# PLC-_-_-V1.net
KiCad netlist of a schematic drawn in Altium Designer
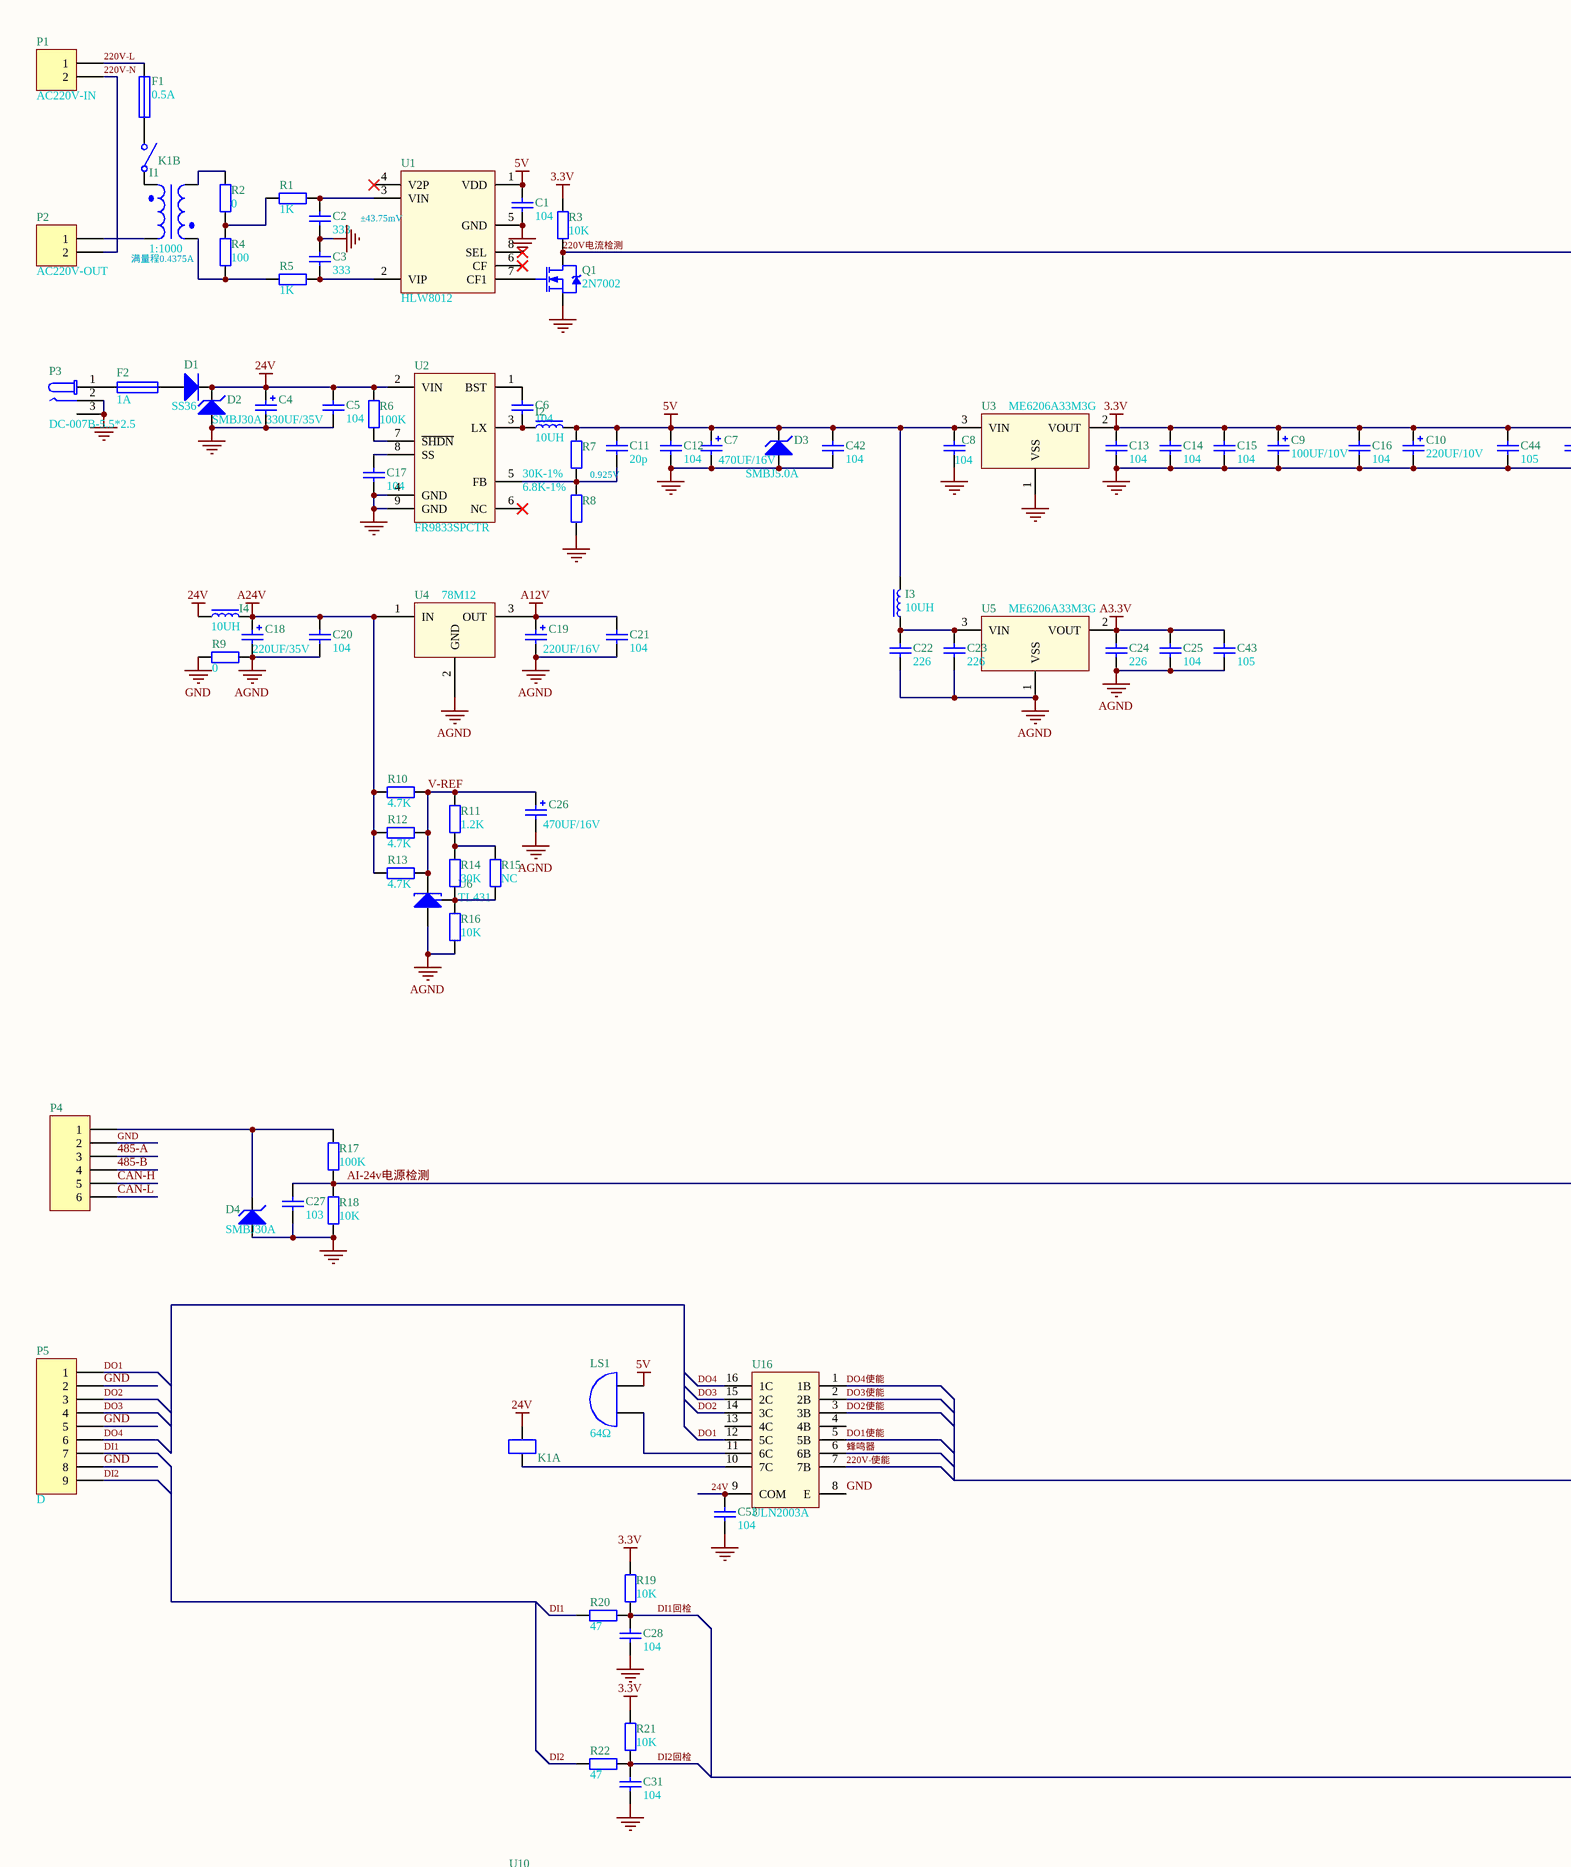
[diagram p0: PLC-无线通讯版-检测板-V1.SchDoc, top left]
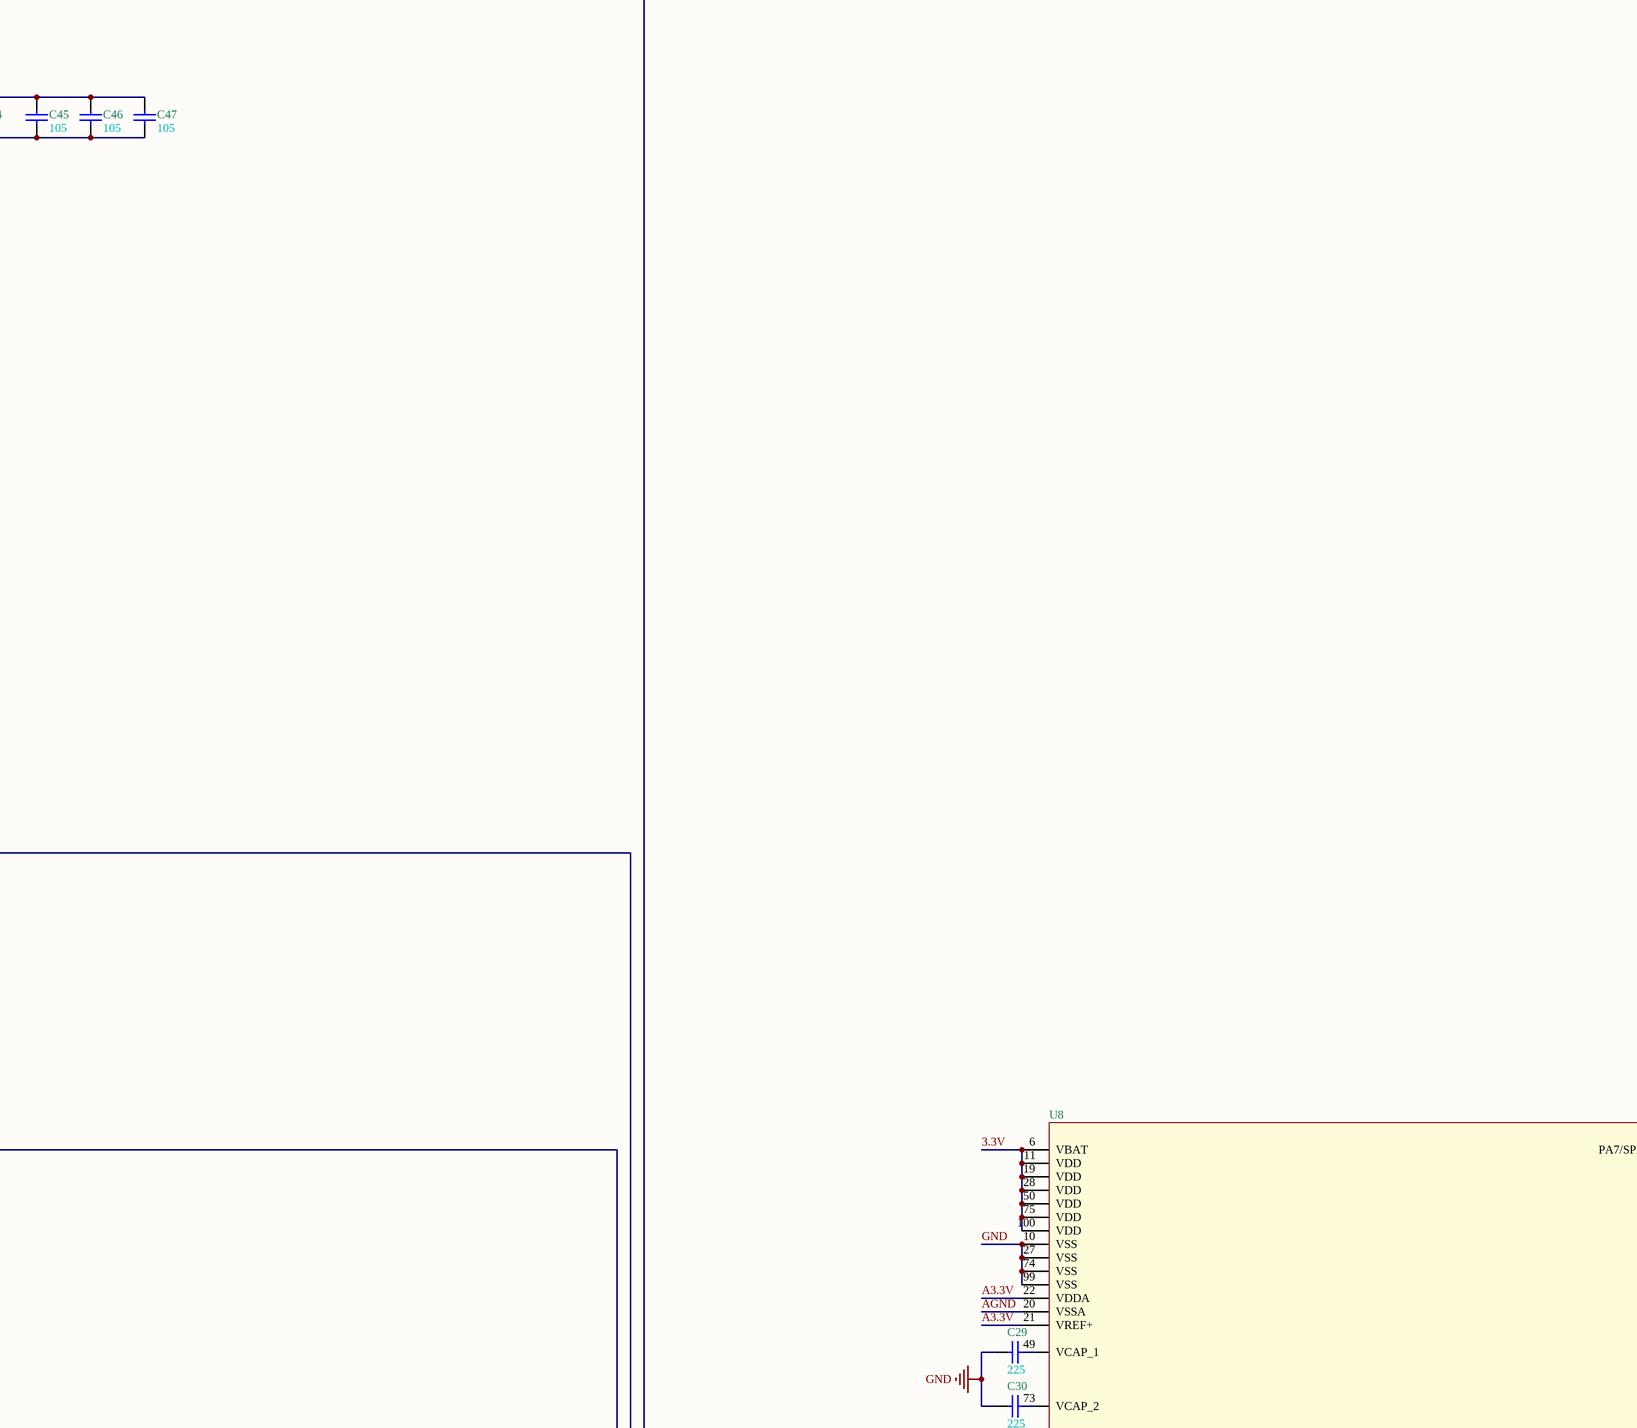
[diagram p1: PLC-无线通讯版-检测板-V1.SchDoc, top middle]
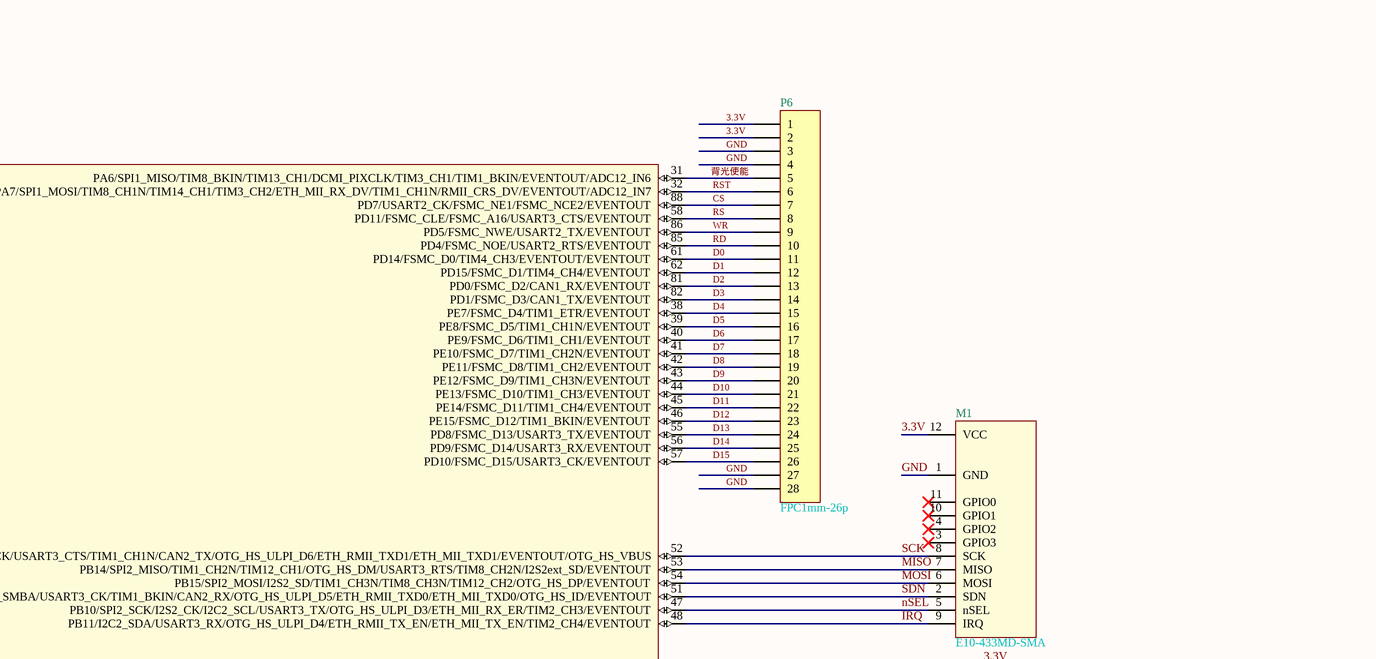
[diagram p2: PLC-无线通讯版-检测板-V1.SchDoc, top right]
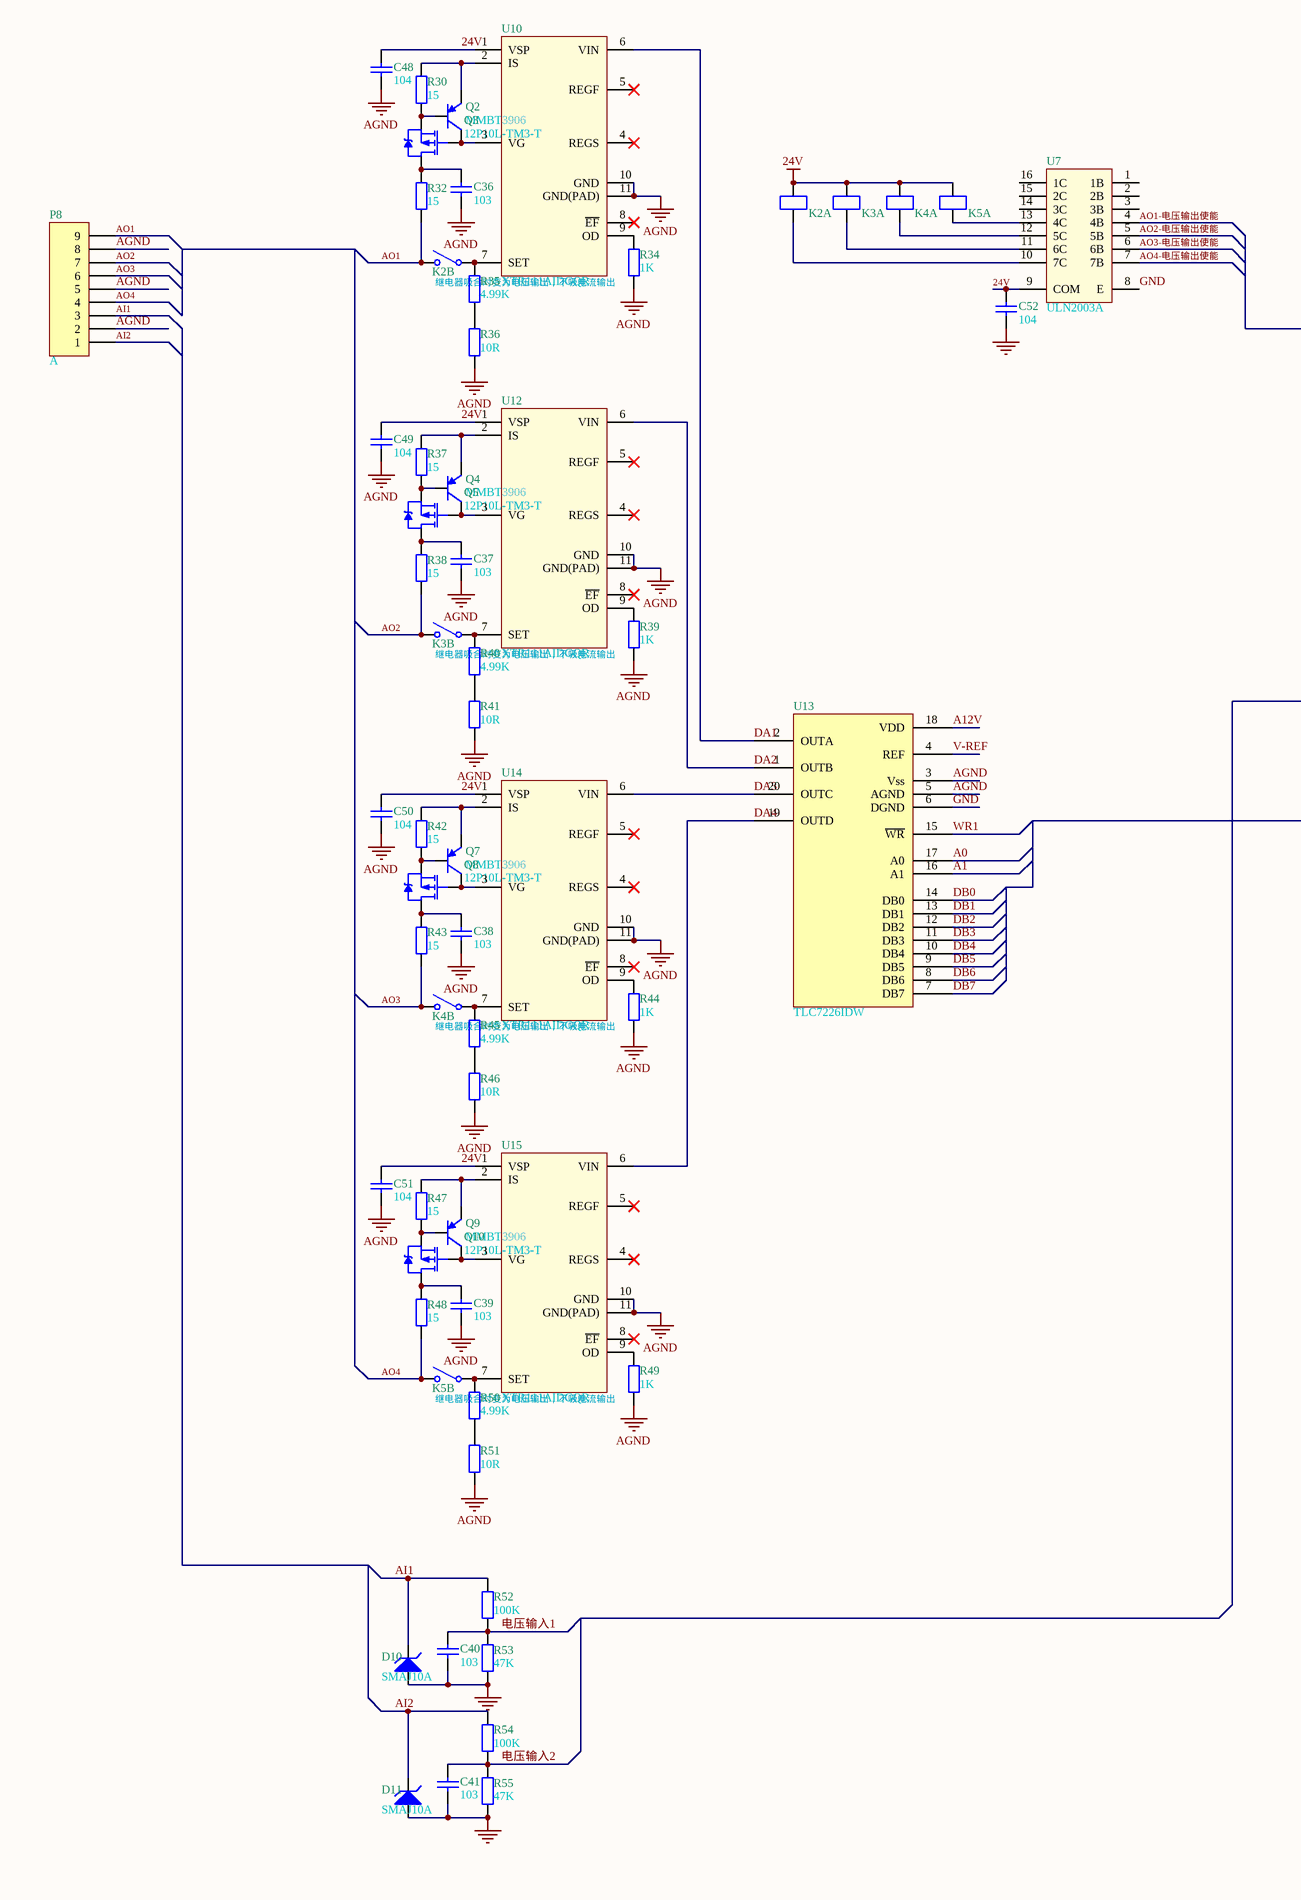
[diagram p3: PLC-无线通讯版-检测板-V1.SchDoc, bottom left]
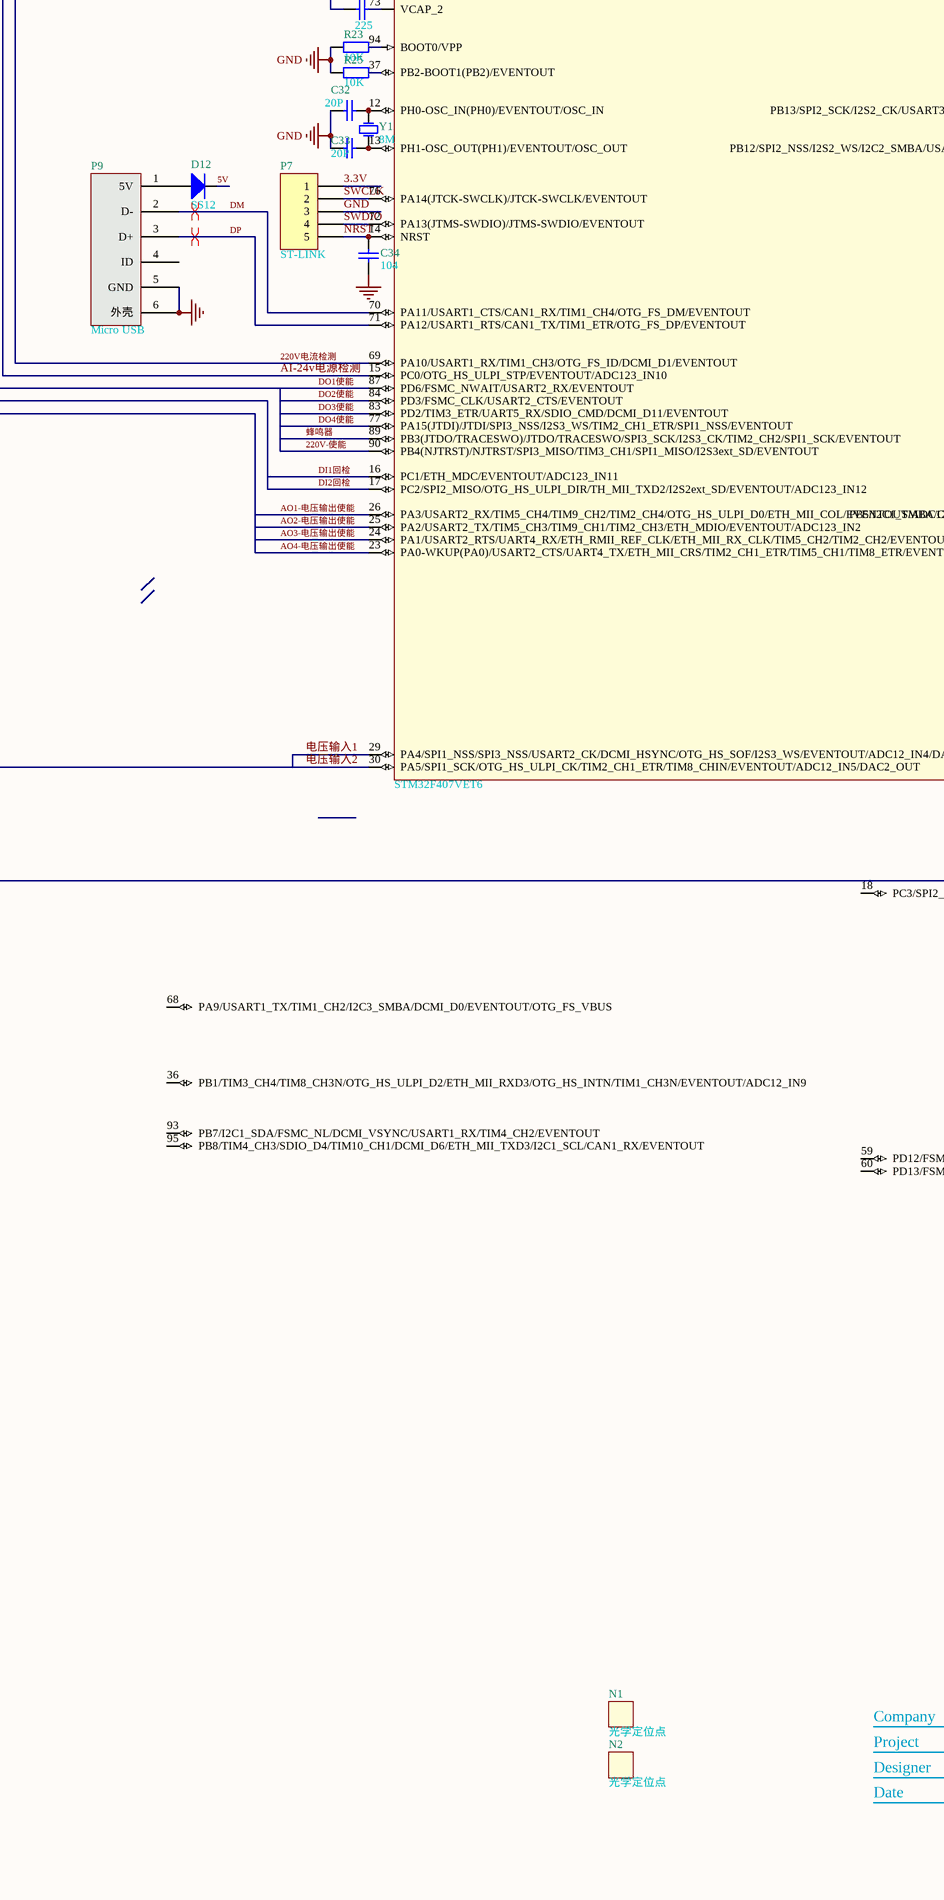
[diagram p4: PLC-无线通讯版-检测板-V1.SchDoc, bottom middle]
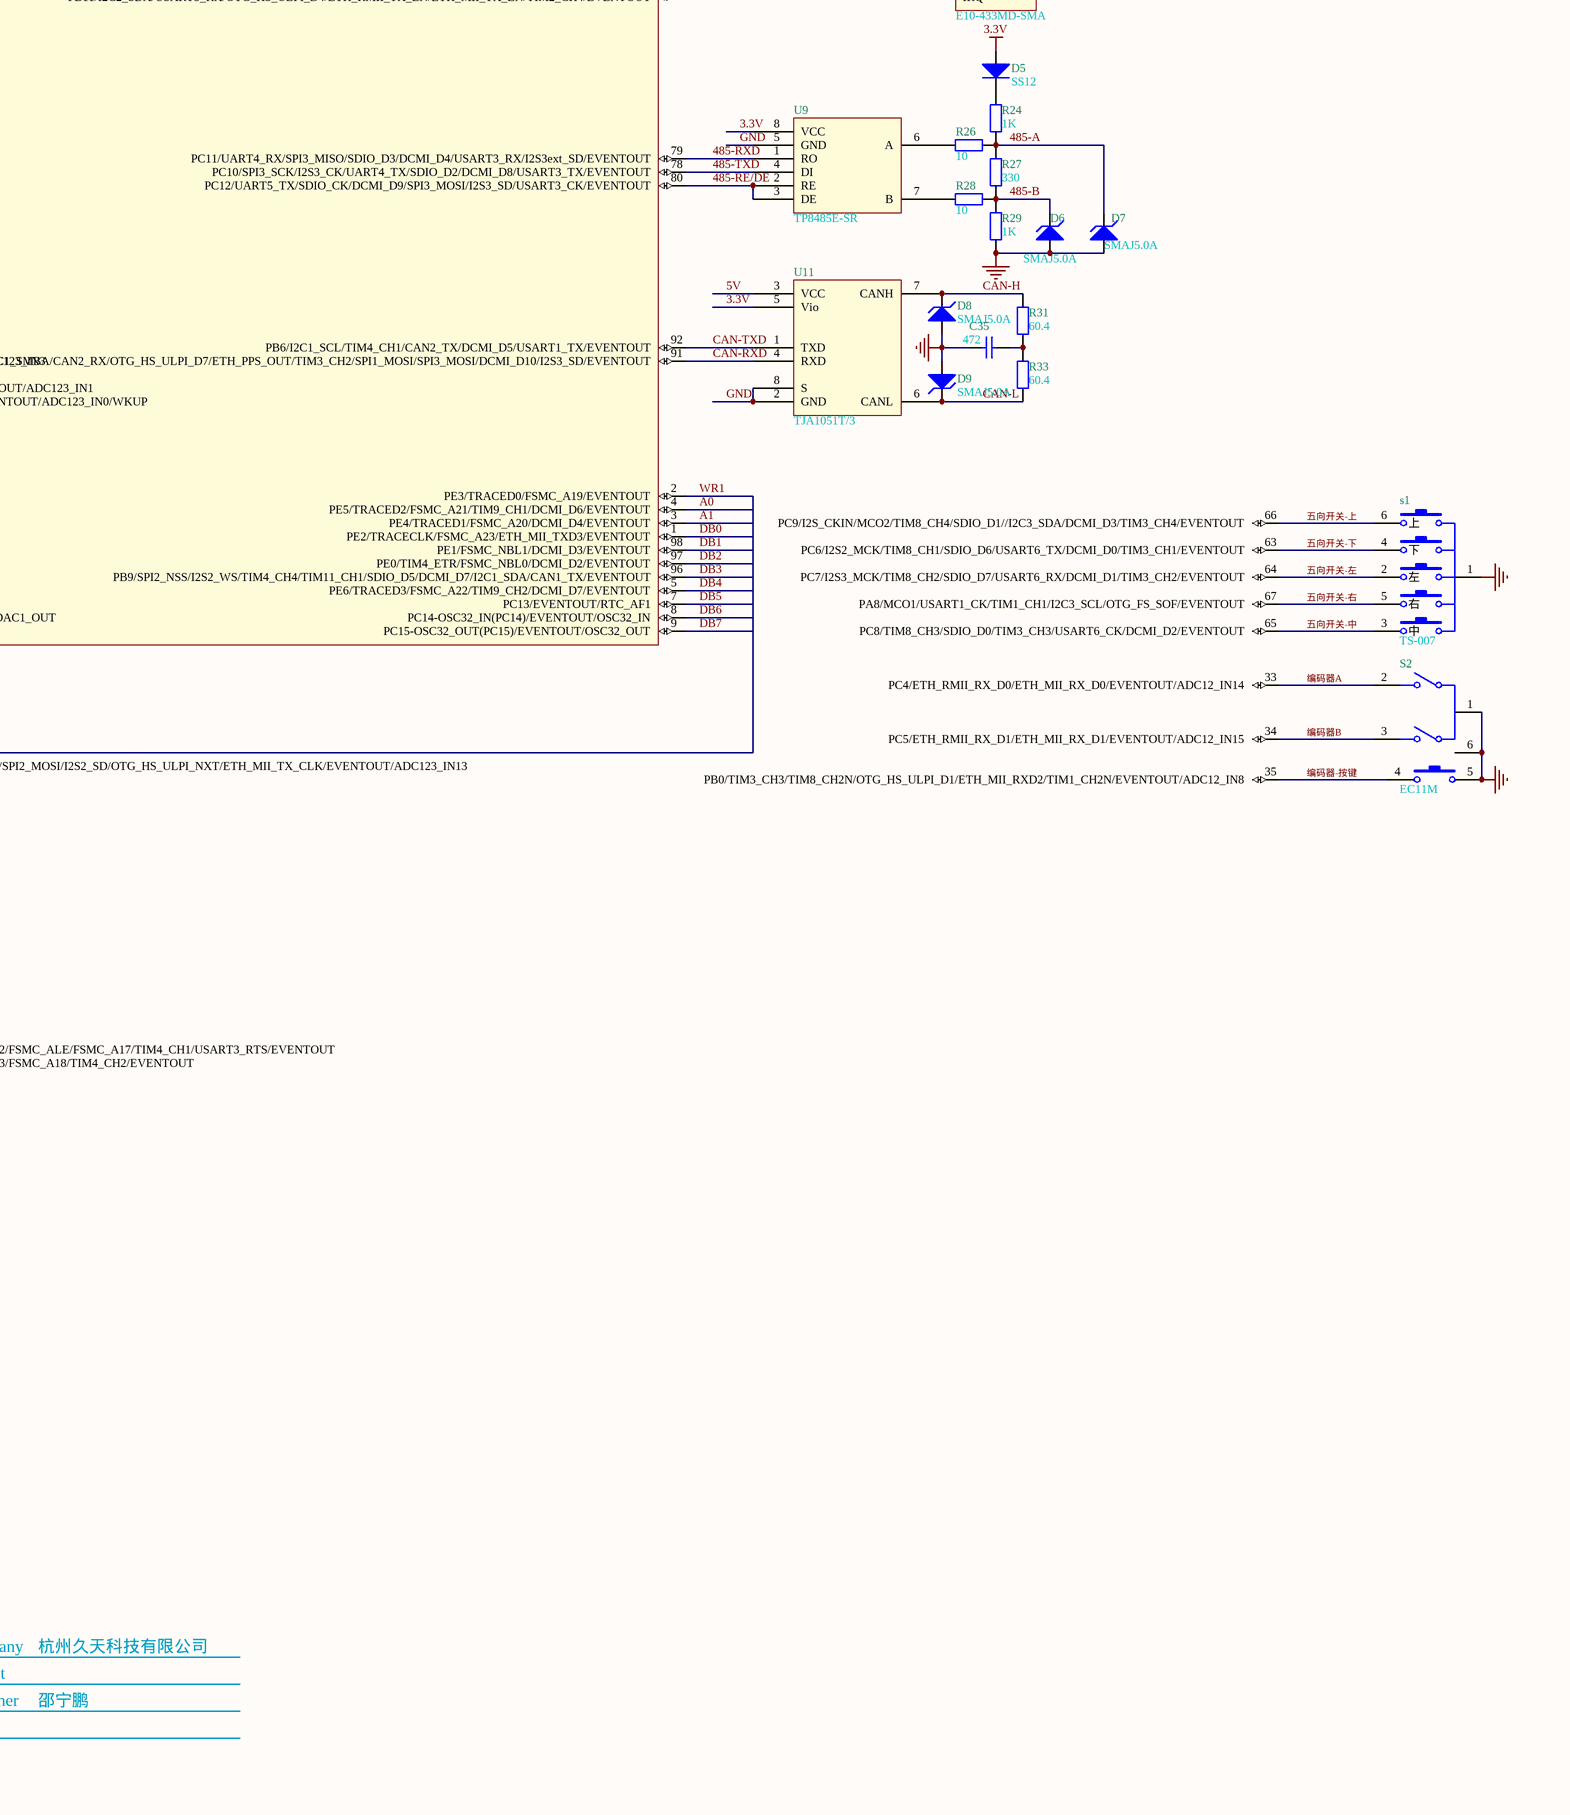
[diagram p5: PLC-无线通讯版-检测板-V1.SchDoc, bottom right]

(export (version "E")
  (design (tool "Eeschema 10.0.6"))
  (components
    (comp (ref "C1")
      (value "104")
      (footprint "C-0603")
      (description "Capacitor")
      (fields (field (name "PUBLISHER") "Altium Limited"))
      (libsource (lib "元件2.0") (part "Cap"))
    )
    (comp (ref "C2")
      (value "333")
      (footprint "C-0603")
      (description "Capacitor")
      (fields (field (name "PUBLISHER") "Altium Limited"))
      (libsource (lib "元件2.0") (part "Cap"))
    )
    (comp (ref "C3")
      (value "333")
      (footprint "C-0603")
      (description "Capacitor")
      (fields (field (name "PUBLISHER") "Altium Limited"))
      (libsource (lib "元件2.0") (part "Cap"))
    )
    (comp (ref "C4")
      (value "330UF/35V")
      (footprint "贴片固态电容8*10-M")
      (description "电解电容")
      (fields (field (name "PUBLISHER") "Altium Limited"))
      (libsource (lib "2电容-V1.0") (part "Cap Pol1"))
    )
    (comp (ref "C5")
      (value "104")
      (footprint "C-0603")
      (description "Capacitor")
      (fields (field (name "PUBLISHER") "Altium Limited"))
      (libsource (lib "元件2.0") (part "Cap"))
    )
    (comp (ref "C6")
      (value "104")
      (footprint "C-0603")
      (description "Capacitor")
      (fields (field (name "PUBLISHER") "Altium Limited"))
      (libsource (lib "元件2.0") (part "Cap"))
    )
    (comp (ref "C7")
      (value "470UF/16V")
      (footprint "贴片固态电容8*10-M")
      (description "Polarized Capacitor (Radial)")
      (fields (field (name "PUBLISHER") "Altium Limited"))
      (libsource (lib "元件2.0") (part "Cap Pol1"))
    )
    (comp (ref "C8")
      (value "104")
      (footprint "C-0603")
      (description "Capacitor")
      (fields (field (name "PUBLISHER") "Altium Limited"))
      (libsource (lib "元件2.0") (part "Cap"))
    )
    (comp (ref "C9")
      (value "100UF/10V")
      (footprint "贴片固态电容5*5.3")
      (description "Polarized Capacitor (Radial)")
      (fields (field (name "PUBLISHER") "Altium Limited"))
      (libsource (lib "元件2.0") (part "Cap Pol1"))
    )
    (comp (ref "C10")
      (value "220UF/10V")
      (footprint "贴片固态电容6.3*5.3-M")
      (description "Polarized Capacitor (Radial)")
      (fields (field (name "PUBLISHER") "Altium Limited"))
      (libsource (lib "元件2.0") (part "Cap Pol1"))
    )
    (comp (ref "C11")
      (value "20p")
      (footprint "C-0603")
      (description "Capacitor")
      (fields (field (name "PUBLISHER") "Altium Limited"))
      (libsource (lib "元件2.0") (part "Cap"))
    )
    (comp (ref "C12")
      (value "104")
      (footprint "C-0603")
      (description "Capacitor")
      (fields (field (name "PUBLISHER") "Altium Limited"))
      (libsource (lib "元件2.0") (part "Cap"))
    )
    (comp (ref "C13")
      (value "104")
      (footprint "C-0603")
      (description "Capacitor")
      (fields (field (name "PUBLISHER") "Altium Limited"))
      (libsource (lib "元件2.0") (part "Cap"))
    )
    (comp (ref "C14")
      (value "104")
      (footprint "C-0603")
      (description "Capacitor")
      (fields (field (name "PUBLISHER") "Altium Limited"))
      (libsource (lib "元件2.0") (part "Cap"))
    )
    (comp (ref "C15")
      (value "104")
      (footprint "C-0603")
      (description "Capacitor")
      (fields (field (name "PUBLISHER") "Altium Limited"))
      (libsource (lib "元件2.0") (part "Cap"))
    )
    (comp (ref "C16")
      (value "104")
      (footprint "C-0603")
      (description "Capacitor")
      (fields (field (name "PUBLISHER") "Altium Limited"))
      (libsource (lib "元件2.0") (part "Cap"))
    )
    (comp (ref "C17")
      (value "104")
      (footprint "C-0603")
      (description "Capacitor")
      (fields (field (name "PUBLISHER") "Altium Limited"))
      (libsource (lib "元件2.0") (part "Cap"))
    )
    (comp (ref "C18")
      (value "220UF/35V")
      (footprint "贴片固态电容8*10-M")
      (description "电解电容")
      (fields (field (name "PUBLISHER") "Altium Limited"))
      (libsource (lib "2电容-V1.0") (part "Cap Pol1"))
    )
    (comp (ref "C19")
      (value "220UF/16V")
      (footprint "贴片固态电容6.3*7.7")
      (description "Polarized Capacitor (Radial)")
      (fields (field (name "PUBLISHER") "Altium Limited"))
      (libsource (lib "元件2.0") (part "Cap Pol1"))
    )
    (comp (ref "C20")
      (value "104")
      (footprint "C-0603")
      (description "Capacitor")
      (fields (field (name "PUBLISHER") "Altium Limited"))
      (libsource (lib "元件2.0") (part "Cap"))
    )
    (comp (ref "C21")
      (value "104")
      (footprint "C-0603")
      (description "Capacitor")
      (fields (field (name "PUBLISHER") "Altium Limited"))
      (libsource (lib "元件2.0") (part "Cap"))
    )
    (comp (ref "C22")
      (value "226")
      (footprint "C-0805")
      (description "Capacitor")
      (fields (field (name "PUBLISHER") "Altium Limited"))
      (libsource (lib "元件2.0") (part "Cap"))
    )
    (comp (ref "C23")
      (value "226")
      (footprint "C-0805")
      (description "Capacitor")
      (fields (field (name "PUBLISHER") "Altium Limited"))
      (libsource (lib "元件2.0") (part "Cap"))
    )
    (comp (ref "C24")
      (value "226")
      (footprint "C-0805")
      (description "Capacitor")
      (fields (field (name "PUBLISHER") "Altium Limited"))
      (libsource (lib "元件2.0") (part "Cap"))
    )
    (comp (ref "C25")
      (value "104")
      (footprint "C-0603")
      (description "Capacitor")
      (fields (field (name "PUBLISHER") "Altium Limited"))
      (libsource (lib "元件2.0") (part "Cap"))
    )
    (comp (ref "C26")
      (value "470UF/16V")
      (footprint "贴片固态电容8*10-M")
      (description "Polarized Capacitor (Radial)")
      (fields (field (name "PUBLISHER") "Altium Limited"))
      (libsource (lib "元件2.0") (part "Cap Pol1"))
    )
    (comp (ref "C27")
      (value "103")
      (footprint "C-0603")
      (description "0805")
      (fields (field (name "PUBLISHER") "Altium Limited"))
      (libsource (lib "2电容-V1.0") (part "Cap-0603"))
    )
    (comp (ref "C28")
      (value "104")
      (footprint "C-0603")
      (description "0805")
      (fields (field (name "PUBLISHER") "Altium Limited"))
      (libsource (lib "2电容-V1.0") (part "Cap-0603"))
    )
    (comp (ref "C29")
      (value "225")
      (footprint "C-0603")
      (description "0805")
      (fields (field (name "PUBLISHER") "Altium Limited"))
      (libsource (lib "2电容-V1.0") (part "Cap-0603"))
    )
    (comp (ref "C30")
      (value "225")
      (footprint "C-0603")
      (description "0805")
      (fields (field (name "PUBLISHER") "Altium Limited"))
      (libsource (lib "2电容-V1.0") (part "Cap-0603"))
    )
    (comp (ref "C31")
      (value "104")
      (footprint "C-0603")
      (description "0805")
      (fields (field (name "PUBLISHER") "Altium Limited"))
      (libsource (lib "2电容-V1.0") (part "Cap-0603"))
    )
    (comp (ref "C32")
      (value "20P")
      (footprint "C-0603")
      (description "0805")
      (fields (field (name "PUBLISHER") "Altium Limited"))
      (libsource (lib "2电容-V1.0") (part "Cap-0603"))
    )
    (comp (ref "C33")
      (value "20P")
      (footprint "C-0603")
      (description "0805")
      (fields (field (name "PUBLISHER") "Altium Limited"))
      (libsource (lib "2电容-V1.0") (part "Cap-0603"))
    )
    (comp (ref "C34")
      (value "104")
      (footprint "C-0603")
      (description "0805")
      (fields (field (name "PUBLISHER") "Altium Limited"))
      (libsource (lib "2电容-V1.0") (part "Cap-0603"))
    )
    (comp (ref "C35")
      (value "472")
      (footprint "C-0603")
      (description "0805")
      (fields (field (name "PUBLISHER") "Altium Limited"))
      (libsource (lib "2电容-V1.0") (part "Cap-0603"))
    )
    (comp (ref "C36")
      (value "103")
      (footprint "C-0603")
      (description "0805")
      (fields (field (name "PUBLISHER") "Altium Limited"))
      (libsource (lib "2电容-V1.0") (part "Cap-0603"))
    )
    (comp (ref "C37")
      (value "103")
      (footprint "C-0603")
      (description "0805")
      (fields (field (name "PUBLISHER") "Altium Limited"))
      (libsource (lib "2电容-V1.0") (part "Cap-0603"))
    )
    (comp (ref "C38")
      (value "103")
      (footprint "C-0603")
      (description "0805")
      (fields (field (name "PUBLISHER") "Altium Limited"))
      (libsource (lib "2电容-V1.0") (part "Cap-0603"))
    )
    (comp (ref "C39")
      (value "103")
      (footprint "C-0603")
      (description "0805")
      (fields (field (name "PUBLISHER") "Altium Limited"))
      (libsource (lib "2电容-V1.0") (part "Cap-0603"))
    )
    (comp (ref "C40")
      (value "103")
      (footprint "C-0603")
      (description "0805")
      (fields (field (name "PUBLISHER") "Altium Limited"))
      (libsource (lib "2电容-V1.0") (part "Cap-0603"))
    )
    (comp (ref "C41")
      (value "103")
      (footprint "C-0603")
      (description "0805")
      (fields (field (name "PUBLISHER") "Altium Limited"))
      (libsource (lib "2电容-V1.0") (part "Cap-0603"))
    )
    (comp (ref "C42")
      (value "104")
      (footprint "C-0603")
      (description "Capacitor")
      (fields (field (name "PUBLISHER") "Altium Limited"))
      (libsource (lib "元件2.0") (part "Cap"))
    )
    (comp (ref "C43")
      (value "105")
      (footprint "C-0603")
      (description "Capacitor")
      (fields (field (name "PUBLISHER") "Altium Limited"))
      (libsource (lib "元件2.0") (part "Cap"))
    )
    (comp (ref "C44")
      (value "105")
      (footprint "C-0603")
      (description "Capacitor")
      (fields (field (name "PUBLISHER") "Altium Limited"))
      (libsource (lib "元件2.0") (part "Cap"))
    )
    (comp (ref "C45")
      (value "105")
      (footprint "C-0603")
      (description "Capacitor")
      (fields (field (name "PUBLISHER") "Altium Limited"))
      (libsource (lib "元件2.0") (part "Cap"))
    )
    (comp (ref "C46")
      (value "105")
      (footprint "C-0603")
      (description "Capacitor")
      (fields (field (name "PUBLISHER") "Altium Limited"))
      (libsource (lib "元件2.0") (part "Cap"))
    )
    (comp (ref "C47")
      (value "105")
      (footprint "C-0603")
      (description "Capacitor")
      (fields (field (name "PUBLISHER") "Altium Limited"))
      (libsource (lib "元件2.0") (part "Cap"))
    )
    (comp (ref "C48")
      (value "104")
      (footprint "C-0603")
      (description "Capacitor")
      (fields (field (name "PUBLISHER") "Altium Limited"))
      (libsource (lib "元件2.0") (part "Cap"))
    )
    (comp (ref "C49")
      (value "104")
      (footprint "C-0603")
      (description "Capacitor")
      (fields (field (name "PUBLISHER") "Altium Limited"))
      (libsource (lib "元件2.0") (part "Cap"))
    )
    (comp (ref "C50")
      (value "104")
      (footprint "C-0603")
      (description "Capacitor")
      (fields (field (name "PUBLISHER") "Altium Limited"))
      (libsource (lib "元件2.0") (part "Cap"))
    )
    (comp (ref "C51")
      (value "104")
      (footprint "C-0603")
      (description "Capacitor")
      (fields (field (name "PUBLISHER") "Altium Limited"))
      (libsource (lib "元件2.0") (part "Cap"))
    )
    (comp (ref "C52")
      (value "104")
      (footprint "C-0603")
      (description "Capacitor")
      (fields (field (name "PUBLISHER") "Altium Limited"))
      (libsource (lib "元件2.0") (part "Cap"))
    )
    (comp (ref "C53")
      (value "104")
      (footprint "C-0603")
      (description "Capacitor")
      (fields (field (name "PUBLISHER") "Altium Limited"))
      (libsource (lib "元件2.0") (part "Cap"))
    )
    (comp (ref "D1")
      (value "SS36")
      (footprint "SMB")
      (description "SMB")
      (fields (field (name "PUBLISHER") "Altium Limited"))
      (libsource (lib "4二极管-V1.1") (part "SS36"))
    )
    (comp (ref "D2")
      (value "SMBJ30A")
      (footprint "SMB-N")
      (description "SMB")
      (libsource (lib "4二极管-V1.1") (part "TVS-1"))
    )
    (comp (ref "D3")
      (value "SMBJ5.0A")
      (footprint "SMB-N")
      (description "SMB")
      (libsource (lib "4二极管-V1.1") (part "TVS-1"))
    )
    (comp (ref "D4")
      (value "SMBJ30A")
      (footprint "SMB")
      (description "SMB")
      (libsource (lib "4二极管-V1.1") (part "TVS-1"))
    )
    (comp (ref "D5")
      (value "SS12")
      (footprint "SOD-523/0603")
      (description "SMA")
      (libsource (lib "4二极管-V1.1") (part "SS14"))
    )
    (comp (ref "D6")
      (value "SMAJ5.0A")
      (footprint "SMA")
      (description "SMB")
      (libsource (lib "4二极管-V1.1") (part "TVS-1"))
    )
    (comp (ref "D7")
      (value "SMAJ5.0A")
      (footprint "SMA")
      (description "SMB")
      (libsource (lib "4二极管-V1.1") (part "TVS-1"))
    )
    (comp (ref "D8")
      (value "SMAJ5.0A")
      (footprint "SMA")
      (description "SMB")
      (libsource (lib "4二极管-V1.1") (part "TVS-1"))
    )
    (comp (ref "D9")
      (value "SMAJ5.0A")
      (footprint "SMA")
      (description "SMB")
      (libsource (lib "4二极管-V1.1") (part "TVS-1"))
    )
    (comp (ref "D10")
      (value "SMAJ10A")
      (footprint "SMA")
      (description "SMB")
      (libsource (lib "4二极管-V1.1") (part "TVS-1"))
    )
    (comp (ref "D11")
      (value "SMAJ10A")
      (footprint "SMA")
      (description "SMB")
      (libsource (lib "4二极管-V1.1") (part "TVS-1"))
    )
    (comp (ref "D12")
      (value "SS12")
      (footprint "SMA")
      (description "SMA")
      (libsource (lib "4二极管-V1.1") (part "SS14"))
    )
    (comp (ref "F1")
      (value "0.5A")
      (footprint "FUSE-3*10带引线")
      (description "Fuse")
      (fields (field (name "PUBLISHER") "Altium Limited"))
      (libsource (lib "11其他元件-V1.0") (part "Fuse 1"))
    )
    (comp (ref "F2")
      (value "1A")
      (footprint "FUSE-1808保险丝座")
      (description "Fuse")
      (fields (field (name "PUBLISHER") "Altium Limited"))
      (libsource (lib "11其他元件-V1.0") (part "Fuse 1"))
    )
    (comp (ref "I1") (value "1:1000") (footprint "EI19*6.5电流互感器") (libsource (lib "3电感-V1.0") (part "电流互感器")))
    (comp (ref "I2")
      (value "10UH")
      (footprint "一体成型电感0630")
      (libsource (lib "3电感-V1.0") (part "Inductance3"))
    )
    (comp (ref "I3") (value "10UH") (footprint "SWPA4030S") (libsource (lib "3电感-V1.0") (part "Inductance3")))
    (comp (ref "I4") (value "10UH") (footprint "SWPA4030S") (libsource (lib "3电感-V1.0") (part "Inductance3")))
    (comp (ref "K1")
      (value "HF49FD-D24-1H11")
      (footprint "HF49FD-D24-1H11")
      (libsource (lib "") (part "HF49FD-D24-1H11_1"))
    )
    (comp (ref "K2")
      (value "HF49FD-D24-1H11")
      (footprint "HF49FD-D24-1H11")
      (libsource (lib "10继电器-V1.0") (part "HF49FD-D24-1H11"))
    )
    (comp (ref "K3")
      (value "HF49FD-D24-1H11")
      (footprint "HF49FD-D24-1H11")
      (libsource (lib "10继电器-V1.0") (part "HF49FD-D24-1H11"))
    )
    (comp (ref "K4")
      (value "HF49FD-D24-1H11")
      (footprint "HF49FD-D24-1H11")
      (libsource (lib "") (part "HF49FD-D24-1H11_1"))
    )
    (comp (ref "K5")
      (value "HF49FD-D24-1H11")
      (footprint "HF49FD-D24-1H11")
      (libsource (lib "") (part "HF49FD-D24-1H11_1"))
    )
    (comp (ref "LS1")
      (value "64Ω")
      (footprint "蜂鸣器 无源 12*8.2")
      (description "Electrical Bell")
      (fields (field (name "PUBLISHER") "Altium Limited"))
      (libsource (lib "11其他元件-V1.0") (part "Bell"))
    )
    (comp (ref "M1")
      (value "E10-433MD-SMA")
      (footprint "E10-433MD-SMA")
      (libsource (lib "6电路模块-V1.0") (part "E10-433MD-SMA"))
    )
    (comp (ref "N1") (value "光学定位点") (footprint "MARK-1mm-3mm") (libsource (lib "11其他元件-V1.0") (part "无引脚")))
    (comp (ref "N2") (value "光学定位点") (footprint "MARK-1mm-3mm") (libsource (lib "11其他元件-V1.0") (part "无引脚")))
    (comp (ref "P1")
      (value "AC220V-IN")
      (footprint "KF2EDGVC-5.08-2P")
      (description "Header, 2-Pin")
      (fields (field (name "PUBLISHER") "Altium Limited"))
      (libsource (lib "5排针-V1.0") (part "Header 2"))
    )
    (comp (ref "P2")
      (value "AC220V-OUT")
      (footprint "KF2EDGVC-5.08-2P")
      (description "Header, 2-Pin")
      (fields (field (name "PUBLISHER") "Altium Limited"))
      (libsource (lib "5排针-V1.0") (part "Header 2"))
    )
    (comp (ref "P3")
      (value "DC-007B-5.5*2.5")
      (footprint "DC-007B")
      (libsource (lib "PJ系列") (part "DC-007B"))
    )
    (comp (ref "P4")
      (value "~")
      (footprint "2EMGKG-5.08-6P")
      (description "Header, 6-Pin")
      (fields (field (name "PUBLISHER") "Altium Limited"))
      (libsource (lib "5排针-V1.0") (part "Header 6"))
    )
    (comp (ref "P5")
      (value "D")
      (footprint "2EMGKG-5.08-9P")
      (description "Header, 9-Pin")
      (fields (field (name "PUBLISHER") "Altium Limited"))
      (libsource (lib "") (part "Header 9_1"))
    )
    (comp (ref "P6")
      (value "FPC1mm-26p")
      (footprint "FPC-0.5mm_26P下接翻盖")
      (description "Header, 28-Pin")
      (fields (field (name "PUBLISHER") "Altium Limited"))
      (libsource (lib "5排针-V1.0") (part "Header 28"))
    )
    (comp (ref "P7")
      (value "ST-LINK")
      (footprint "HDR1X5")
      (description "Header, 5-Pin")
      (fields (field (name "PUBLISHER") "Altium Limited"))
      (libsource (lib "5排针-V1.0") (part "Header 5"))
    )
    (comp (ref "P8")
      (value "A")
      (footprint "2EMGKG-5.08-9P")
      (description "Header, 9-Pin")
      (fields (field (name "PUBLISHER") "Altium Limited"))
      (libsource (lib "5排针-V1.0") (part "Header 9"))
    )
    (comp (ref "P9")
      (value "Micro USB")
      (footprint "MICRO-USB-牛角插板-无卷边")
      (libsource (lib "11其他元件-V1.0") (part "USB-5_A"))
    )
    (comp (ref "Q1") (value "2N7002") (footprint "SOT-23") (libsource (lib "4二极管-V1.1") (part "2N7002")))
    (comp (ref "Q2")
      (value "MMBT3906")
      (footprint "SOT-23")
      (description "PNP SOT-23")
      (fields (field (name "PUBLISHER") "Altium Limited"))
      (libsource (lib "4二极管-V1.1") (part "S8550"))
    )
    (comp (ref "Q3")
      (value "12P10L-TM3-T")
      (footprint "TO-251-N")
      (libsource (lib "4二极管-V1.1") (part "12P10L-TM3-T"))
    )
    (comp (ref "Q4")
      (value "MMBT3906")
      (footprint "SOT-23")
      (description "PNP SOT-23")
      (fields (field (name "PUBLISHER") "Altium Limited"))
      (libsource (lib "4二极管-V1.1") (part "S8550"))
    )
    (comp (ref "Q5")
      (value "12P10L-TM3-T")
      (footprint "TO-251-N")
      (libsource (lib "4二极管-V1.1") (part "12P10L-TM3-T"))
    )
    (comp (ref "Q7")
      (value "MMBT3906")
      (footprint "SOT-23")
      (description "PNP SOT-23")
      (fields (field (name "PUBLISHER") "Altium Limited"))
      (libsource (lib "4二极管-V1.1") (part "S8550"))
    )
    (comp (ref "Q8")
      (value "12P10L-TM3-T")
      (footprint "TO-251-N")
      (libsource (lib "4二极管-V1.1") (part "12P10L-TM3-T"))
    )
    (comp (ref "Q9")
      (value "MMBT3906")
      (footprint "SOT-23")
      (description "PNP SOT-23")
      (fields (field (name "PUBLISHER") "Altium Limited"))
      (libsource (lib "4二极管-V1.1") (part "S8550"))
    )
    (comp (ref "Q10")
      (value "12P10L-TM3-T")
      (footprint "TO-251-N")
      (libsource (lib "4二极管-V1.1") (part "12P10L-TM3-T"))
    )
    (comp (ref "R1")
      (value "1K")
      (footprint "R-0603")
      (description "0603")
      (fields (field (name "PUBLISHER") "Altium Limited"))
      (libsource (lib "") (part "Res2-0603_3"))
    )
    (comp (ref "R2")
      (value "0")
      (footprint "R-1206")
      (description "0603")
      (fields (field (name "PUBLISHER") "Altium Limited"))
      (libsource (lib "") (part "Res2-0603_1"))
    )
    (comp (ref "R3")
      (value "10K")
      (footprint "R-0603")
      (description "0603")
      (fields (field (name "PUBLISHER") "Altium Limited"))
      (libsource (lib "1电阻-V1.0") (part "Res2-0603"))
    )
    (comp (ref "R4")
      (value "100")
      (footprint "R-1206")
      (description "0603")
      (fields (field (name "PUBLISHER") "Altium Limited"))
      (libsource (lib "") (part "Res2-0603_1"))
    )
    (comp (ref "R5")
      (value "1K")
      (footprint "R-0603")
      (description "0603")
      (fields (field (name "PUBLISHER") "Altium Limited"))
      (libsource (lib "") (part "Res2-0603_3"))
    )
    (comp (ref "R6")
      (value "100K")
      (footprint "R-0603")
      (description "0603")
      (fields (field (name "PUBLISHER") "Altium Limited"))
      (libsource (lib "") (part "Res2-0603_2"))
    )
    (comp (ref "R7")
      (value "30K-1%")
      (footprint "R-0603")
      (description "0603")
      (fields (field (name "PUBLISHER") "Altium Limited"))
      (libsource (lib "") (part "Res2-0603_2"))
    )
    (comp (ref "R8")
      (value "6.8K-1%")
      (footprint "R-0603")
      (description "0603")
      (fields (field (name "PUBLISHER") "Altium Limited"))
      (libsource (lib "") (part "Res2-0603_2"))
    )
    (comp (ref "R9")
      (value "0")
      (footprint "R-1206")
      (description "0603")
      (fields (field (name "PUBLISHER") "Altium Limited"))
      (libsource (lib "1电阻-V1.0") (part "Res2-0603"))
    )
    (comp (ref "R10")
      (value "4.7K")
      (footprint "R-1206")
      (description "0603")
      (fields (field (name "PUBLISHER") "Altium Limited"))
      (libsource (lib "") (part "Res2-0603_2"))
    )
    (comp (ref "R11")
      (value "1.2K")
      (footprint "R-0603")
      (description "0603")
      (fields (field (name "PUBLISHER") "Altium Limited"))
      (libsource (lib "1电阻-V1.0") (part "Res2-0603"))
    )
    (comp (ref "R12")
      (value "4.7K")
      (footprint "R-1206")
      (description "0603")
      (fields (field (name "PUBLISHER") "Altium Limited"))
      (libsource (lib "") (part "Res2-0603_2"))
    )
    (comp (ref "R13")
      (value "4.7K")
      (footprint "R-1206")
      (description "0603")
      (fields (field (name "PUBLISHER") "Altium Limited"))
      (libsource (lib "") (part "Res2-0603_2"))
    )
    (comp (ref "R14")
      (value "30K")
      (footprint "R-0603")
      (description "0603")
      (fields (field (name "PUBLISHER") "Altium Limited"))
      (libsource (lib "1电阻-V1.0") (part "Res2-0603"))
    )
    (comp (ref "R15")
      (value "NC")
      (footprint "R-0603")
      (description "0603")
      (fields (field (name "PUBLISHER") "Altium Limited"))
      (libsource (lib "1电阻-V1.0") (part "Res2-0603"))
    )
    (comp (ref "R16")
      (value "10K")
      (footprint "R-0603")
      (description "0603")
      (fields (field (name "PUBLISHER") "Altium Limited"))
      (libsource (lib "1电阻-V1.0") (part "Res2-0603"))
    )
    (comp (ref "R17")
      (value "100K")
      (footprint "R-1206")
      (description "0603")
      (fields (field (name "PUBLISHER") "Altium Limited"))
      (libsource (lib "1电阻-V1.0") (part "Res2-0603"))
    )
    (comp (ref "R18")
      (value "10K")
      (footprint "R-1206")
      (description "0603")
      (fields (field (name "PUBLISHER") "Altium Limited"))
      (libsource (lib "1电阻-V1.0") (part "Res2-0603"))
    )
    (comp (ref "R19")
      (value "10K")
      (footprint "R-0603")
      (description "0603")
      (fields (field (name "PUBLISHER") "Altium Limited"))
      (libsource (lib "1电阻-V1.0") (part "Res2-0603"))
    )
    (comp (ref "R20")
      (value "47")
      (footprint "R-0603")
      (description "0603")
      (fields (field (name "PUBLISHER") "Altium Limited"))
      (libsource (lib "") (part "Res2-0603_2"))
    )
    (comp (ref "R21")
      (value "10K")
      (footprint "R-0603")
      (description "0603")
      (fields (field (name "PUBLISHER") "Altium Limited"))
      (libsource (lib "1电阻-V1.0") (part "Res2-0603"))
    )
    (comp (ref "R22")
      (value "47")
      (footprint "R-0603")
      (description "0603")
      (fields (field (name "PUBLISHER") "Altium Limited"))
      (libsource (lib "") (part "Res2-0603_2"))
    )
    (comp (ref "R23")
      (value "10K")
      (footprint "R-0603")
      (description "0603")
      (fields (field (name "PUBLISHER") "Altium Limited"))
      (libsource (lib "") (part "Res2-0603_2"))
    )
    (comp (ref "R24")
      (value "1K")
      (footprint "R-0603")
      (description "Resistor")
      (fields (field (name "PUBLISHER") "Altium Limited"))
      (libsource (lib "元件2.0") (part "Res2"))
    )
    (comp (ref "R25")
      (value "10K")
      (footprint "R-0603")
      (description "0603")
      (fields (field (name "PUBLISHER") "Altium Limited"))
      (libsource (lib "") (part "Res2-0603_2"))
    )
    (comp (ref "R26")
      (value "10")
      (footprint "R-0805")
      (description "Resistor")
      (fields (field (name "PUBLISHER") "Altium Limited"))
      (libsource (lib "") (part "Res2_1"))
    )
    (comp (ref "R27")
      (value "330")
      (footprint "R-1206-M")
      (description "Resistor")
      (fields (field (name "PUBLISHER") "Altium Limited"))
      (libsource (lib "Miscellaneous Devices") (part "Res2"))
    )
    (comp (ref "R28")
      (value "10")
      (footprint "R-0805")
      (description "Resistor")
      (fields (field (name "PUBLISHER") "Altium Limited"))
      (libsource (lib "") (part "Res2_1"))
    )
    (comp (ref "R29")
      (value "1K")
      (footprint "R-0603")
      (description "Resistor")
      (fields (field (name "PUBLISHER") "Altium Limited"))
      (libsource (lib "") (part "Res2_1"))
    )
    (comp (ref "R30")
      (value "15")
      (footprint "R-0805")
      (description "0603")
      (fields (field (name "PUBLISHER") "Altium Limited"))
      (libsource (lib "") (part "Res2-0603_2"))
    )
    (comp (ref "R31")
      (value "60.4")
      (footprint "R-1206")
      (description "Resistor")
      (fields (field (name "PUBLISHER") "Altium Limited"))
      (libsource (lib "Miscellaneous Devices") (part "Res2"))
    )
    (comp (ref "R32")
      (value "15")
      (footprint "R-0805")
      (description "0603")
      (fields (field (name "PUBLISHER") "Altium Limited"))
      (libsource (lib "") (part "Res2-0603_2"))
    )
    (comp (ref "R33")
      (value "60.4")
      (footprint "R-1206")
      (description "Resistor")
      (fields (field (name "PUBLISHER") "Altium Limited"))
      (libsource (lib "Miscellaneous Devices") (part "Res2"))
    )
    (comp (ref "R34")
      (value "1K")
      (footprint "R-0603")
      (description "0603")
      (fields (field (name "PUBLISHER") "Altium Limited"))
      (libsource (lib "") (part "Res2-0603_2"))
    )
    (comp (ref "R35")
      (value "4.99K")
      (footprint "R-0603")
      (description "0603")
      (fields (field (name "PUBLISHER") "Altium Limited"))
      (libsource (lib "") (part "Res2-0603_2"))
    )
    (comp (ref "R36")
      (value "10R")
      (footprint "R-0603")
      (description "0603")
      (fields (field (name "PUBLISHER") "Altium Limited"))
      (libsource (lib "") (part "Res2-0603_2"))
    )
    (comp (ref "R37")
      (value "15")
      (footprint "R-0805")
      (description "0603")
      (fields (field (name "PUBLISHER") "Altium Limited"))
      (libsource (lib "") (part "Res2-0603_2"))
    )
    (comp (ref "R38")
      (value "15")
      (footprint "R-0805")
      (description "0603")
      (fields (field (name "PUBLISHER") "Altium Limited"))
      (libsource (lib "") (part "Res2-0603_2"))
    )
    (comp (ref "R39")
      (value "1K")
      (footprint "R-0603")
      (description "0603")
      (fields (field (name "PUBLISHER") "Altium Limited"))
      (libsource (lib "") (part "Res2-0603_2"))
    )
    (comp (ref "R40")
      (value "4.99K")
      (footprint "R-0603")
      (description "0603")
      (fields (field (name "PUBLISHER") "Altium Limited"))
      (libsource (lib "") (part "Res2-0603_2"))
    )
    (comp (ref "R41")
      (value "10R")
      (footprint "R-0603")
      (description "0603")
      (fields (field (name "PUBLISHER") "Altium Limited"))
      (libsource (lib "") (part "Res2-0603_2"))
    )
    (comp (ref "R42")
      (value "15")
      (footprint "R-0805")
      (description "0603")
      (fields (field (name "PUBLISHER") "Altium Limited"))
      (libsource (lib "") (part "Res2-0603_2"))
    )
    (comp (ref "R43")
      (value "15")
      (footprint "R-0805")
      (description "0603")
      (fields (field (name "PUBLISHER") "Altium Limited"))
      (libsource (lib "") (part "Res2-0603_2"))
    )
    (comp (ref "R44")
      (value "1K")
      (footprint "R-0603")
      (description "0603")
      (fields (field (name "PUBLISHER") "Altium Limited"))
      (libsource (lib "") (part "Res2-0603_2"))
    )
    (comp (ref "R45")
      (value "4.99K")
      (footprint "R-0603")
      (description "0603")
      (fields (field (name "PUBLISHER") "Altium Limited"))
      (libsource (lib "") (part "Res2-0603_2"))
    )
    (comp (ref "R46")
      (value "10R")
      (footprint "R-0603")
      (description "0603")
      (fields (field (name "PUBLISHER") "Altium Limited"))
      (libsource (lib "") (part "Res2-0603_2"))
    )
    (comp (ref "R47")
      (value "15")
      (footprint "R-0805")
      (description "0603")
      (fields (field (name "PUBLISHER") "Altium Limited"))
      (libsource (lib "") (part "Res2-0603_2"))
    )
    (comp (ref "R48")
      (value "15")
      (footprint "R-0805")
      (description "0603")
      (fields (field (name "PUBLISHER") "Altium Limited"))
      (libsource (lib "") (part "Res2-0603_2"))
    )
    (comp (ref "R49")
      (value "1K")
      (footprint "R-0603")
      (description "0603")
      (fields (field (name "PUBLISHER") "Altium Limited"))
      (libsource (lib "") (part "Res2-0603_2"))
    )
    (comp (ref "R50")
      (value "4.99K")
      (footprint "R-0603")
      (description "0603")
      (fields (field (name "PUBLISHER") "Altium Limited"))
      (libsource (lib "") (part "Res2-0603_2"))
    )
    (comp (ref "R51")
      (value "10R")
      (footprint "R-0603")
      (description "0603")
      (fields (field (name "PUBLISHER") "Altium Limited"))
      (libsource (lib "") (part "Res2-0603_2"))
    )
    (comp (ref "R52")
      (value "100K")
      (footprint "R-1206")
      (description "0603")
      (fields (field (name "PUBLISHER") "Altium Limited"))
      (libsource (lib "1电阻-V1.0") (part "Res2-0603"))
    )
    (comp (ref "R53")
      (value "47K")
      (footprint "R-1206")
      (description "0603")
      (fields (field (name "PUBLISHER") "Altium Limited"))
      (libsource (lib "1电阻-V1.0") (part "Res2-0603"))
    )
    (comp (ref "R54")
      (value "100K")
      (footprint "R-1206")
      (description "0603")
      (fields (field (name "PUBLISHER") "Altium Limited"))
      (libsource (lib "1电阻-V1.0") (part "Res2-0603"))
    )
    (comp (ref "R55")
      (value "47K")
      (footprint "R-1206")
      (description "0603")
      (fields (field (name "PUBLISHER") "Altium Limited"))
      (libsource (lib "1电阻-V1.0") (part "Res2-0603"))
    )
    (comp (ref "s1")
      (value "TS-007")
      (footprint "TS-007")
      (description "五向开关")
      (libsource (lib "开关-V1") (part "TS-007"))
    )
    (comp (ref "S2") (value "EC11M") (footprint "EC11M") (libsource (lib "开关-V1") (part "EC11M")))
    (comp (ref "U1")
      (value "HLW8012")
      (footprint "SOP-8-M")
      (description "单相多功能计量芯片")
      (libsource (lib "8集成电路-V1.1") (part "HLW8012"))
    )
    (comp (ref "U2")
      (value "FR9833SPCTR")
      (footprint "SOP-8-EXPOSED PAD")
      (description "DC-DC降压")
      (libsource (lib "电源芯片DC-DC") (part "FR9833SPCTR"))
    )
    (comp (ref "U3")
      (value "ME6206A33M3G")
      (footprint "SOT-23")
      (description "LDO稳压 SOT-23")
      (libsource (lib "电源芯片-线性稳压-V1") (part "ME6206A33M3G"))
    )
    (comp (ref "U4")
      (value "78M12")
      (footprint "TO-252")
      (description "TO-252")
      (libsource (lib "电源芯片-线性稳压-V1") (part "78M05"))
    )
    (comp (ref "U5")
      (value "ME6206A33M3G")
      (footprint "SOT-23")
      (description "LDO稳压 SOT-23")
      (libsource (lib "电源芯片-线性稳压-V1") (part "ME6206A33M3G"))
    )
    (comp (ref "U6")
      (value "TL431")
      (footprint "SOT-23")
      (description "稳压芯片 SOT-23")
      (libsource (lib "8集成电路-V1.1") (part "TL431"))
    )
    (comp (ref "U7") (value "ULN2003A") (footprint "SOP-16-M") (libsource (lib "电机驱动器V1") (part "ULN2003A")))
    (comp (ref "U8")
      (value "STM32F407VET6")
      (footprint "LQFP100-N")
      (libsource (lib "9单片机-V1.0") (part "STM32F407VET6"))
    )
    (comp (ref "U9")
      (value "TP8485E-SR")
      (footprint "SOP-8-N")
      (description "RS485总线转串口")
      (libsource (lib "集成电路1.0") (part "MAX3082"))
    )
    (comp (ref "U10")
      (value "XTR111AIDGQR")
      (footprint "MSOP-10(11)-M")
      (description "4-20ma输出")
      (libsource (lib "8集成电路-V1.1") (part "XTR111"))
    )
    (comp (ref "U11")
      (value "TJA1051T/3")
      (footprint "SOP-8-N")
      (libsource (lib "通讯-V1") (part "TJA1051T/3"))
    )
    (comp (ref "U12")
      (value "XTR111AIDGQR")
      (footprint "MSOP-10(11)-M")
      (description "4-20ma输出")
      (libsource (lib "8集成电路-V1.1") (part "XTR111"))
    )
    (comp (ref "U13")
      (value "TLC7226IDW")
      (footprint "SOP-20")
      (libsource (lib "DAC-V1") (part "TLC7226IDW"))
    )
    (comp (ref "U14")
      (value "XTR111AIDGQR")
      (footprint "MSOP-10(11)-M")
      (description "4-20ma输出")
      (libsource (lib "8集成电路-V1.1") (part "XTR111"))
    )
    (comp (ref "U15")
      (value "XTR111AIDGQR")
      (footprint "MSOP-10(11)-M")
      (description "4-20ma输出")
      (libsource (lib "8集成电路-V1.1") (part "XTR111"))
    )
    (comp (ref "U16") (value "ULN2003A") (footprint "SOP-16-M") (libsource (lib "电机驱动器V1") (part "ULN2003A")))
    (comp (ref "Y1") (value "8M") (footprint "HC-49SMD") (libsource (lib "11其他元件-V1.0") (part "晶振")))
  )
  (nets
    (net (code "1") (name "/220V-L") (class "Default")
      (node (ref "F1") (pin "1") (pinfunction "1_1") (pintype "passive"))
      (node (ref "P1") (pin "1") (pinfunction "1_1") (pintype "passive"))
    )
    (net (code "2") (name "/220V-N") (class "Default")
      (node (ref "P1") (pin "2") (pinfunction "2_2") (pintype "passive"))
      (node (ref "P2") (pin "2") (pinfunction "2_2") (pintype "passive"))
    )
    (net (code "3") (name "/220V-使能") (class "Default")
      (node (ref "U16") (pin "7") (pinfunction "7B_7") (pintype "passive"))
      (node (ref "U8") (pin "90") (pinfunction "PB4(NJTRST)/NJTRST/SPI3_MISO/TIM3_CH1/SPI1_MISO/I2S3ext_SD/EVENTOUT_90") (pintype "bidirectional"))
    )
    (net (code "4") (name "/220V电流检测") (class "Default")
      (node (ref "Q1") (pin "3") (pinfunction "D_3") (pintype "passive"))
      (node (ref "R3") (pin "1") (pinfunction "1_1") (pintype "passive"))
      (node (ref "U8") (pin "69") (pinfunction "PA10/USART1_RX/TIM1_CH3/OTG_FS_ID/DCMI_D1/EVENTOUT_69") (pintype "bidirectional"))
    )
    (net (code "5") (name "/485-A") (class "Default")
      (node (ref "D7") (pin "2") (pinfunction "K_2") (pintype "passive"))
      (node (ref "P4") (pin "3") (pinfunction "3_3") (pintype "passive"))
      (node (ref "R24") (pin "2") (pinfunction "2_2") (pintype "passive"))
      (node (ref "R26") (pin "1") (pinfunction "1_1") (pintype "passive"))
      (node (ref "R27") (pin "2") (pinfunction "2_2") (pintype "passive"))
    )
    (net (code "6") (name "/485-B") (class "Default")
      (node (ref "D6") (pin "2") (pinfunction "K_2") (pintype "passive"))
      (node (ref "P4") (pin "4") (pinfunction "4_4") (pintype "passive"))
      (node (ref "R27") (pin "1") (pinfunction "1_1") (pintype "passive"))
      (node (ref "R28") (pin "1") (pinfunction "1_1") (pintype "passive"))
      (node (ref "R29") (pin "2") (pinfunction "2_2") (pintype "passive"))
    )
    (net (code "7") (name "/485-RE{slash}DE") (class "Default")
      (node (ref "U8") (pin "80") (pinfunction "PC12/UART5_TX/SDIO_CK/DCMI_D9/SPI3_MOSI/I2S3_SD/USART3_CK/EVENTOUT_80") (pintype "bidirectional"))
      (node (ref "U9") (pin "2") (pinfunction "RE_2") (pintype "passive"))
      (node (ref "U9") (pin "3") (pinfunction "DE_3") (pintype "passive"))
    )
    (net (code "8") (name "/485-RXD") (class "Default")
      (node (ref "U8") (pin "79") (pinfunction "PC11/UART4_RX/SPI3_MISO/SDIO_D3/DCMI_D4/USART3_RX/I2S3ext_SD/EVENTOUT_79") (pintype "bidirectional"))
      (node (ref "U9") (pin "1") (pinfunction "RO_1") (pintype "passive"))
    )
    (net (code "9") (name "/485-TXD") (class "Default")
      (node (ref "U8") (pin "78") (pinfunction "PC10/SPI3_SCK/I2S3_CK/UART4_TX/SDIO_D2/DCMI_D8/USART3_TX/EVENTOUT_78") (pintype "bidirectional"))
      (node (ref "U9") (pin "4") (pinfunction "DI_4") (pintype "passive"))
    )
    (net (code "10") (name "/A0") (class "Default")
      (node (ref "U13") (pin "17") (pinfunction "A0_17") (pintype "passive"))
      (node (ref "U8") (pin "4") (pinfunction "PE5/TRACED2/FSMC_A21/TIM9_CH1/DCMI_D6/EVENTOUT_4") (pintype "bidirectional"))
    )
    (net (code "11") (name "/A1") (class "Default")
      (node (ref "U13") (pin "16") (pinfunction "A1_16") (pintype "passive"))
      (node (ref "U8") (pin "3") (pinfunction "PE4/TRACED1/FSMC_A20/DCMI_D4/EVENTOUT_3") (pintype "bidirectional"))
    )
    (net (code "12") (name "/AI-24v电源检测") (class "Default")
      (node (ref "C27") (pin "2") (pinfunction "2_2") (pintype "passive"))
      (node (ref "R17") (pin "1") (pinfunction "1_1") (pintype "passive"))
      (node (ref "R18") (pin "2") (pinfunction "2_2") (pintype "passive"))
      (node (ref "U8") (pin "15") (pinfunction "PC0/OTG_HS_ULPI_STP/EVENTOUT/ADC123_IN10_15") (pintype "bidirectional"))
    )
    (net (code "13") (name "/AI1") (class "Default")
      (node (ref "D10") (pin "2") (pinfunction "K_2") (pintype "passive"))
      (node (ref "P8") (pin "3") (pinfunction "3_3") (pintype "passive"))
      (node (ref "R52") (pin "2") (pinfunction "2_2") (pintype "passive"))
    )
    (net (code "14") (name "/AI2") (class "Default")
      (node (ref "D11") (pin "2") (pinfunction "K_2") (pintype "passive"))
      (node (ref "P8") (pin "1") (pinfunction "1_1") (pintype "passive"))
      (node (ref "R54") (pin "2") (pinfunction "2_2") (pintype "passive"))
    )
    (net (code "15") (name "/AO1") (class "Default")
      (node (ref "K2") (pin "4") (pinfunction "4_4") (pintype "passive"))
      (node (ref "P8") (pin "9") (pinfunction "9_9") (pintype "passive"))
      (node (ref "R32") (pin "2") (pinfunction "2_2") (pintype "passive"))
    )
    (net (code "16") (name "/AO1-电压输出使能") (class "Default")
      (node (ref "U7") (pin "4") (pinfunction "4B_4") (pintype "passive"))
      (node (ref "U8") (pin "26") (pinfunction "PA3/USART2_RX/TIM5_CH4/TIM9_CH2/TIM2_CH4/OTG_HS_ULPI_D0/ETH_MII_COL/EVENTOUT/ADC123_IN3_26") (pintype "bidirectional"))
    )
    (net (code "17") (name "/AO2") (class "Default")
      (node (ref "K3") (pin "4") (pinfunction "4_4") (pintype "passive"))
      (node (ref "P8") (pin "7") (pinfunction "7_7") (pintype "passive"))
      (node (ref "R38") (pin "2") (pinfunction "2_2") (pintype "passive"))
    )
    (net (code "18") (name "/AO2-电压输出使能") (class "Default")
      (node (ref "U7") (pin "5") (pinfunction "5B_5") (pintype "passive"))
      (node (ref "U8") (pin "25") (pinfunction "PA2/USART2_TX/TIM5_CH3/TIM9_CH1/TIM2_CH3/ETH_MDIO/EVENTOUT/ADC123_IN2_25") (pintype "bidirectional"))
    )
    (net (code "19") (name "/AO3") (class "Default")
      (node (ref "K4") (pin "4") (pinfunction "4_4") (pintype "passive"))
      (node (ref "P8") (pin "6") (pinfunction "6_6") (pintype "passive"))
      (node (ref "R43") (pin "2") (pinfunction "2_2") (pintype "passive"))
    )
    (net (code "20") (name "/AO3-电压输出使能") (class "Default")
      (node (ref "U7") (pin "6") (pinfunction "6B_6") (pintype "passive"))
      (node (ref "U8") (pin "24") (pinfunction "PA1/USART2_RTS/UART4_RX/ETH_RMII_REF_CLK/ETH_MII_RX_CLK/TIM5_CH2/TIM2_CH2/EVENTOUT/ADC123_IN1_24") (pintype "bidirectional"))
    )
    (net (code "21") (name "/AO4") (class "Default")
      (node (ref "K5") (pin "4") (pinfunction "4_4") (pintype "passive"))
      (node (ref "P8") (pin "4") (pinfunction "4_4") (pintype "passive"))
      (node (ref "R48") (pin "2") (pinfunction "2_2") (pintype "passive"))
    )
    (net (code "22") (name "/AO4-电压输出使能") (class "Default")
      (node (ref "U7") (pin "7") (pinfunction "7B_7") (pintype "passive"))
      (node (ref "U8") (pin "23") (pinfunction "PA0-WKUP(PA0)/USART2_CTS/UART4_TX/ETH_MII_CRS/TIM2_CH1_ETR/TIM5_CH1/TIM8_ETR/EVENTOUT/ADC123_IN0/WKUP_23") (pintype "bidirectional"))
    )
    (net (code "23") (name "/CAN-H") (class "Default")
      (node (ref "D8") (pin "2") (pinfunction "K_2") (pintype "passive"))
      (node (ref "P4") (pin "5") (pinfunction "5_5") (pintype "passive"))
      (node (ref "R31") (pin "2") (pinfunction "2_2") (pintype "passive"))
      (node (ref "U11") (pin "7") (pinfunction "CANH_7") (pintype "passive"))
    )
    (net (code "24") (name "/CAN-L") (class "Default")
      (node (ref "D9") (pin "2") (pinfunction "K_2") (pintype "passive"))
      (node (ref "P4") (pin "6") (pinfunction "6_6") (pintype "passive"))
      (node (ref "R33") (pin "1") (pinfunction "1_1") (pintype "passive"))
      (node (ref "U11") (pin "6") (pinfunction "CANL_6") (pintype "passive"))
    )
    (net (code "25") (name "/CAN-RXD") (class "Default")
      (node (ref "U11") (pin "4") (pinfunction "RXD_4") (pintype "passive"))
      (node (ref "U8") (pin "91") (pinfunction "PB5/I2C1_SMBA/CAN2_RX/OTG_HS_ULPI_D7/ETH_PPS_OUT/TIM3_CH2/SPI1_MOSI/SPI3_MOSI/DCMI_D10/I2S3_SD/EVENTOUT_91") (pintype "bidirectional"))
    )
    (net (code "26") (name "/CAN-TXD") (class "Default")
      (node (ref "U11") (pin "1") (pinfunction "TXD_1") (pintype "passive"))
      (node (ref "U8") (pin "92") (pinfunction "PB6/I2C1_SCL/TIM4_CH1/CAN2_TX/DCMI_D5/USART1_TX/EVENTOUT_92") (pintype "bidirectional"))
    )
    (net (code "27") (name "/CS") (class "Default")
      (node (ref "P6") (pin "7") (pinfunction "7_7") (pintype "passive"))
      (node (ref "U8") (pin "88") (pinfunction "PD7/USART2_CK/FSMC_NE1/FSMC_NCE2/EVENTOUT_88") (pintype "bidirectional"))
    )
    (net (code "28") (name "/D0") (class "Default")
      (node (ref "P6") (pin "11") (pinfunction "11_11") (pintype "passive"))
      (node (ref "U8") (pin "61") (pinfunction "PD14/FSMC_D0/TIM4_CH3/EVENTOUT/EVENTOUT_61") (pintype "bidirectional"))
    )
    (net (code "29") (name "/D1") (class "Default")
      (node (ref "P6") (pin "12") (pinfunction "12_12") (pintype "passive"))
      (node (ref "U8") (pin "62") (pinfunction "PD15/FSMC_D1/TIM4_CH4/EVENTOUT_62") (pintype "bidirectional"))
    )
    (net (code "30") (name "/D2") (class "Default")
      (node (ref "P6") (pin "13") (pinfunction "13_13") (pintype "passive"))
      (node (ref "U8") (pin "81") (pinfunction "PD0/FSMC_D2/CAN1_RX/EVENTOUT_81") (pintype "bidirectional"))
    )
    (net (code "31") (name "/D3") (class "Default")
      (node (ref "P6") (pin "14") (pinfunction "14_14") (pintype "passive"))
      (node (ref "U8") (pin "82") (pinfunction "PD1/FSMC_D3/CAN1_TX/EVENTOUT_82") (pintype "bidirectional"))
    )
    (net (code "32") (name "/D4") (class "Default")
      (node (ref "P6") (pin "15") (pinfunction "15_15") (pintype "passive"))
      (node (ref "U8") (pin "38") (pinfunction "PE7/FSMC_D4/TIM1_ETR/EVENTOUT_38") (pintype "bidirectional"))
    )
    (net (code "33") (name "/D5") (class "Default")
      (node (ref "P6") (pin "16") (pinfunction "16_16") (pintype "passive"))
      (node (ref "U8") (pin "39") (pinfunction "PE8/FSMC_D5/TIM1_CH1N/EVENTOUT_39") (pintype "bidirectional"))
    )
    (net (code "34") (name "/D6") (class "Default")
      (node (ref "P6") (pin "17") (pinfunction "17_17") (pintype "passive"))
      (node (ref "U8") (pin "40") (pinfunction "PE9/FSMC_D6/TIM1_CH1/EVENTOUT_40") (pintype "bidirectional"))
    )
    (net (code "35") (name "/D7") (class "Default")
      (node (ref "P6") (pin "18") (pinfunction "18_18") (pintype "passive"))
      (node (ref "U8") (pin "41") (pinfunction "PE10/FSMC_D7/TIM1_CH2N/EVENTOUT_41") (pintype "bidirectional"))
    )
    (net (code "36") (name "/D8") (class "Default")
      (node (ref "P6") (pin "19") (pinfunction "19_19") (pintype "passive"))
      (node (ref "U8") (pin "42") (pinfunction "PE11/FSMC_D8/TIM1_CH2/EVENTOUT_42") (pintype "bidirectional"))
    )
    (net (code "37") (name "/D9") (class "Default")
      (node (ref "P6") (pin "20") (pinfunction "20_20") (pintype "passive"))
      (node (ref "U8") (pin "43") (pinfunction "PE12/FSMC_D9/TIM1_CH3N/EVENTOUT_43") (pintype "bidirectional"))
    )
    (net (code "38") (name "/D10") (class "Default")
      (node (ref "P6") (pin "21") (pinfunction "21_21") (pintype "passive"))
      (node (ref "U8") (pin "44") (pinfunction "PE13/FSMC_D10/TIM1_CH3/EVENTOUT_44") (pintype "bidirectional"))
    )
    (net (code "39") (name "/D11") (class "Default")
      (node (ref "P6") (pin "22") (pinfunction "22_22") (pintype "passive"))
      (node (ref "U8") (pin "45") (pinfunction "PE14/FSMC_D11/TIM1_CH4/EVENTOUT_45") (pintype "bidirectional"))
    )
    (net (code "40") (name "/D12") (class "Default")
      (node (ref "P6") (pin "23") (pinfunction "23_23") (pintype "passive"))
      (node (ref "U8") (pin "46") (pinfunction "PE15/FSMC_D12/TIM1_BKIN/EVENTOUT_46") (pintype "bidirectional"))
    )
    (net (code "41") (name "/D13") (class "Default")
      (node (ref "P6") (pin "24") (pinfunction "24_24") (pintype "passive"))
      (node (ref "U8") (pin "55") (pinfunction "PD8/FSMC_D13/USART3_TX/EVENTOUT_55") (pintype "bidirectional"))
    )
    (net (code "42") (name "/D14") (class "Default")
      (node (ref "P6") (pin "25") (pinfunction "25_25") (pintype "passive"))
      (node (ref "U8") (pin "56") (pinfunction "PD9/FSMC_D14/USART3_RX/EVENTOUT_56") (pintype "bidirectional"))
    )
    (net (code "43") (name "/D15") (class "Default")
      (node (ref "P6") (pin "26") (pinfunction "26_26") (pintype "passive"))
      (node (ref "U8") (pin "57") (pinfunction "PD10/FSMC_D15/USART3_CK/EVENTOUT_57") (pintype "bidirectional"))
    )
    (net (code "44") (name "/DA1") (class "Default")
      (node (ref "U10") (pin "6") (pinfunction "VIN_6") (pintype "passive"))
      (node (ref "U13") (pin "2") (pinfunction "OUTA_2") (pintype "passive"))
    )
    (net (code "45") (name "/DA2") (class "Default")
      (node (ref "U12") (pin "6") (pinfunction "VIN_6") (pintype "passive"))
      (node (ref "U13") (pin "1") (pinfunction "OUTB_1") (pintype "passive"))
    )
    (net (code "46") (name "/DA3") (class "Default")
      (node (ref "U13") (pin "20") (pinfunction "OUTC_20") (pintype "passive"))
      (node (ref "U14") (pin "6") (pinfunction "VIN_6") (pintype "passive"))
    )
    (net (code "47") (name "/DA4") (class "Default")
      (node (ref "U13") (pin "19") (pinfunction "OUTD_19") (pintype "passive"))
      (node (ref "U15") (pin "6") (pinfunction "VIN_6") (pintype "passive"))
    )
    (net (code "48") (name "/DB0") (class "Default")
      (node (ref "U13") (pin "14") (pinfunction "DB0_14") (pintype "passive"))
      (node (ref "U8") (pin "1") (pinfunction "PE2/TRACECLK/FSMC_A23/ETH_MII_TXD3/EVENTOUT_1") (pintype "bidirectional"))
    )
    (net (code "49") (name "/DB1") (class "Default")
      (node (ref "U13") (pin "13") (pinfunction "DB1_13") (pintype "passive"))
      (node (ref "U8") (pin "98") (pinfunction "PE1/FSMC_NBL1/DCMI_D3/EVENTOUT_98") (pintype "bidirectional"))
    )
    (net (code "50") (name "/DB2") (class "Default")
      (node (ref "U13") (pin "12") (pinfunction "DB2_12") (pintype "passive"))
      (node (ref "U8") (pin "97") (pinfunction "PE0/TIM4_ETR/FSMC_NBL0/DCMI_D2/EVENTOUT_97") (pintype "bidirectional"))
    )
    (net (code "51") (name "/DB3") (class "Default")
      (node (ref "U13") (pin "11") (pinfunction "DB3_11") (pintype "passive"))
      (node (ref "U8") (pin "96") (pinfunction "PB9/SPI2_NSS/I2S2_WS/TIM4_CH4/TIM11_CH1/SDIO_D5/DCMI_D7/I2C1_SDA/CAN1_TX/EVENTOUT_96") (pintype "bidirectional"))
    )
    (net (code "52") (name "/DB4") (class "Default")
      (node (ref "U13") (pin "10") (pinfunction "DB4_10") (pintype "passive"))
      (node (ref "U8") (pin "5") (pinfunction "PE6/TRACED3/FSMC_A22/TIM9_CH2/DCMI_D7/EVENTOUT_5") (pintype "bidirectional"))
    )
    (net (code "53") (name "/DB5") (class "Default")
      (node (ref "U13") (pin "9") (pinfunction "DB5_9") (pintype "passive"))
      (node (ref "U8") (pin "7") (pinfunction "PC13/EVENTOUT/RTC_AF1_7") (pintype "bidirectional"))
    )
    (net (code "54") (name "/DB6") (class "Default")
      (node (ref "U13") (pin "8") (pinfunction "DB6_8") (pintype "passive"))
      (node (ref "U8") (pin "8") (pinfunction "PC14-OSC32_IN(PC14)/EVENTOUT/OSC32_IN_8") (pintype "bidirectional"))
    )
    (net (code "55") (name "/DB7") (class "Default")
      (node (ref "U13") (pin "7") (pinfunction "DB7_7") (pintype "passive"))
      (node (ref "U8") (pin "9") (pinfunction "PC15-OSC32_OUT(PC15)/EVENTOUT/OSC32_OUT_9") (pintype "bidirectional"))
    )
    (net (code "56") (name "/DI1") (class "Default")
      (node (ref "P5") (pin "7") (pinfunction "7_7") (pintype "passive"))
      (node (ref "R20") (pin "2") (pinfunction "2_2") (pintype "passive"))
    )
    (net (code "57") (name "/DI1回检") (class "Default")
      (node (ref "C28") (pin "2") (pinfunction "2_2") (pintype "passive"))
      (node (ref "R19") (pin "1") (pinfunction "1_1") (pintype "passive"))
      (node (ref "R20") (pin "1") (pinfunction "1_1") (pintype "passive"))
      (node (ref "U8") (pin "16") (pinfunction "PC1/ETH_MDC/EVENTOUT/ADC123_IN11_16") (pintype "bidirectional"))
    )
    (net (code "58") (name "/DI2") (class "Default")
      (node (ref "P5") (pin "9") (pinfunction "9_9") (pintype "passive"))
      (node (ref "R22") (pin "2") (pinfunction "2_2") (pintype "passive"))
    )
    (net (code "59") (name "/DI2回检") (class "Default")
      (node (ref "C31") (pin "2") (pinfunction "2_2") (pintype "passive"))
      (node (ref "R21") (pin "1") (pinfunction "1_1") (pintype "passive"))
      (node (ref "R22") (pin "1") (pinfunction "1_1") (pintype "passive"))
      (node (ref "U8") (pin "17") (pinfunction "PC2/SPI2_MISO/OTG_HS_ULPI_DIR/TH_MII_TXD2/I2S2ext_SD/EVENTOUT/ADC123_IN12_17") (pintype "bidirectional"))
    )
    (net (code "60") (name "/DM") (class "Default")
      (node (ref "P9") (pin "2") (pinfunction "D-_2") (pintype "passive"))
      (node (ref "U8") (pin "70") (pinfunction "PA11/USART1_CTS/CAN1_RX/TIM1_CH4/OTG_FS_DM/EVENTOUT_70") (pintype "bidirectional"))
    )
    (net (code "61") (name "/DO1") (class "Default")
      (node (ref "P5") (pin "1") (pinfunction "1_1") (pintype "passive"))
      (node (ref "U16") (pin "12") (pinfunction "5C_12") (pintype "passive"))
    )
    (net (code "62") (name "/DO1使能") (class "Default")
      (node (ref "U16") (pin "5") (pinfunction "5B_5") (pintype "passive"))
      (node (ref "U8") (pin "87") (pinfunction "PD6/FSMC_NWAIT/USART2_RX/EVENTOUT_87") (pintype "bidirectional"))
    )
    (net (code "63") (name "/DO2") (class "Default")
      (node (ref "P5") (pin "3") (pinfunction "3_3") (pintype "passive"))
      (node (ref "U16") (pin "14") (pinfunction "3C_14") (pintype "passive"))
    )
    (net (code "64") (name "/DO2使能") (class "Default")
      (node (ref "U16") (pin "3") (pinfunction "3B_3") (pintype "passive"))
      (node (ref "U8") (pin "84") (pinfunction "PD3/FSMC_CLK/USART2_CTS/EVENTOUT_84") (pintype "bidirectional"))
    )
    (net (code "65") (name "/DO3") (class "Default")
      (node (ref "P5") (pin "4") (pinfunction "4_4") (pintype "passive"))
      (node (ref "U16") (pin "15") (pinfunction "2C_15") (pintype "passive"))
    )
    (net (code "66") (name "/DO3使能") (class "Default")
      (node (ref "U16") (pin "2") (pinfunction "2B_2") (pintype "passive"))
      (node (ref "U8") (pin "83") (pinfunction "PD2/TIM3_ETR/UART5_RX/SDIO_CMD/DCMI_D11/EVENTOUT_83") (pintype "bidirectional"))
    )
    (net (code "67") (name "/DO4") (class "Default")
      (node (ref "P5") (pin "6") (pinfunction "6_6") (pintype "passive"))
      (node (ref "U16") (pin "16") (pinfunction "1C_16") (pintype "passive"))
    )
    (net (code "68") (name "/DO4使能") (class "Default")
      (node (ref "U16") (pin "1") (pinfunction "1B_1") (pintype "passive"))
      (node (ref "U8") (pin "77") (pinfunction "PA15(JTDI)/JTDI/SPI3_NSS/I2S3_WS/TIM2_CH1_ETR/SPI1_NSS/EVENTOUT_77") (pintype "bidirectional"))
    )
    (net (code "69") (name "/DP") (class "Default")
      (node (ref "P9") (pin "3") (pinfunction "D+_3") (pintype "passive"))
      (node (ref "U8") (pin "71") (pinfunction "PA12/USART1_RTS/CAN1_TX/TIM1_ETR/OTG_FS_DP/EVENTOUT_71") (pintype "bidirectional"))
    )
    (net (code "70") (name "/IRQ") (class "Default")
      (node (ref "M1") (pin "9") (pinfunction "IRQ_9") (pintype "passive"))
      (node (ref "U8") (pin "48") (pinfunction "PB11/I2C2_SDA/USART3_RX/OTG_HS_ULPI_D4/ETH_RMII_TX_EN/ETH_MII_TX_EN/TIM2_CH4/EVENTOUT_48") (pintype "bidirectional"))
    )
    (net (code "71") (name "/MISO") (class "Default")
      (node (ref "M1") (pin "7") (pinfunction "MISO_7") (pintype "passive"))
      (node (ref "U8") (pin "53") (pinfunction "PB14/SPI2_MISO/TIM1_CH2N/TIM12_CH1/OTG_HS_DM/USART3_RTS/TIM8_CH2N/I2S2ext_SD/EVENTOUT_53") (pintype "bidirectional"))
    )
    (net (code "72") (name "/MOSI") (class "Default")
      (node (ref "M1") (pin "6") (pinfunction "MOSI_6") (pintype "passive"))
      (node (ref "U8") (pin "54") (pinfunction "PB15/SPI2_MOSI/I2S2_SD/TIM1_CH3N/TIM8_CH3N/TIM12_CH2/OTG_HS_DP/EVENTOUT_54") (pintype "bidirectional"))
    )
    (net (code "73") (name "/NRST") (class "Default")
      (node (ref "C34") (pin "2") (pinfunction "2_2") (pintype "passive"))
      (node (ref "P7") (pin "5") (pinfunction "5_5") (pintype "passive"))
      (node (ref "U8") (pin "14") (pinfunction "NRST_14") (pintype "bidirectional"))
    )
    (net (code "74") (name "/RD") (class "Default")
      (node (ref "P6") (pin "10") (pinfunction "10_10") (pintype "passive"))
      (node (ref "U8") (pin "85") (pinfunction "PD4/FSMC_NOE/USART2_RTS/EVENTOUT_85") (pintype "bidirectional"))
    )
    (net (code "75") (name "/RS") (class "Default")
      (node (ref "P6") (pin "8") (pinfunction "8_8") (pintype "passive"))
      (node (ref "U8") (pin "58") (pinfunction "PD11/FSMC_CLE/FSMC_A16/USART3_CTS/EVENTOUT_58") (pintype "bidirectional"))
    )
    (net (code "76") (name "/RST") (class "Default")
      (node (ref "P6") (pin "6") (pinfunction "6_6") (pintype "passive"))
      (node (ref "U8") (pin "32") (pinfunction "PA7/SPI1_MOSI/TIM8_CH1N/TIM14_CH1/TIM3_CH2/ETH_MII_RX_DV/TIM1_CH1N/RMII_CRS_DV/EVENTOUT/ADC12_IN7_32") (pintype "bidirectional"))
    )
    (net (code "77") (name "/SCK") (class "Default")
      (node (ref "M1") (pin "8") (pinfunction "SCK_8") (pintype "passive"))
      (node (ref "U8") (pin "52") (pinfunction "PB13/SPI2_SCK/I2S2_CK/USART3_CTS/TIM1_CH1N/CAN2_TX/OTG_HS_ULPI_D6/ETH_RMII_TXD1/ETH_MII_TXD1/EVENTOUT/OTG_HS_VBUS_52") (pintype "bidirectional"))
    )
    (net (code "78") (name "/SDN") (class "Default")
      (node (ref "M1") (pin "2") (pinfunction "SDN_2") (pintype "passive"))
      (node (ref "U8") (pin "51") (pinfunction "PB12/SPI2_NSS/I2S2_WS/I2C2_SMBA/USART3_CK/TIM1_BKIN/CAN2_RX/OTG_HS_ULPI_D5/ETH_RMII_TXD0/ETH_MII_TXD0/OTG_HS_ID/EVENTOUT_51") (pintype "bidirectional"))
    )
    (net (code "79") (name "/SWCLK") (class "Default")
      (node (ref "P7") (pin "2") (pinfunction "2_2") (pintype "passive"))
      (node (ref "U8") (pin "76") (pinfunction "PA14(JTCK-SWCLK)/JTCK-SWCLK/EVENTOUT_76") (pintype "bidirectional"))
    )
    (net (code "80") (name "/SWDIO") (class "Default")
      (node (ref "P7") (pin "4") (pinfunction "4_4") (pintype "passive"))
      (node (ref "U8") (pin "72") (pinfunction "PA13(JTMS-SWDIO)/JTMS-SWDIO/EVENTOUT_72") (pintype "bidirectional"))
    )
    (net (code "81") (name "/V-REF") (class "Default")
      (node (ref "C26") (pin "1") (pinfunction "1_1") (pintype "passive"))
      (node (ref "R10") (pin "1") (pinfunction "1_1") (pintype "passive"))
      (node (ref "R11") (pin "2") (pinfunction "2_2") (pintype "passive"))
      (node (ref "R12") (pin "1") (pinfunction "1_1") (pintype "passive"))
      (node (ref "R13") (pin "1") (pinfunction "1_1") (pintype "passive"))
      (node (ref "U13") (pin "4") (pinfunction "REF_4") (pintype "passive"))
      (node (ref "U6") (pin "2") (pinfunction "K_2") (pintype "passive"))
    )
    (net (code "82") (name "/WR") (class "Default")
      (node (ref "P6") (pin "9") (pinfunction "9_9") (pintype "passive"))
      (node (ref "U8") (pin "86") (pinfunction "PD5/FSMC_NWE/USART2_TX/EVENTOUT_86") (pintype "bidirectional"))
    )
    (net (code "83") (name "/WR1") (class "Default")
      (node (ref "U13") (pin "15") (pinfunction "~{WR}_15") (pintype "passive"))
      (node (ref "U8") (pin "2") (pinfunction "PE3/TRACED0/FSMC_A19/EVENTOUT_2") (pintype "bidirectional"))
    )
    (net (code "84") (name "/nSEL") (class "Default")
      (node (ref "M1") (pin "5") (pinfunction "nSEL_5") (pintype "passive"))
      (node (ref "U8") (pin "47") (pinfunction "PB10/SPI2_SCK/I2S2_CK/I2C2_SCL/USART3_TX/OTG_HS_ULPI_D3/ETH_MII_RX_ER/TIM2_CH3/EVENTOUT_47") (pintype "bidirectional"))
    )
    (net (code "85") (name "/五向开关-上") (class "Default")
      (node (ref "U8") (pin "66") (pinfunction "PC9/I2S_CKIN/MCO2/TIM8_CH4/SDIO_D1//I2C3_SDA/DCMI_D3/TIM3_CH4/EVENTOUT_66") (pintype "bidirectional"))
      (node (ref "s1") (pin "6") (pinfunction "上_6") (pintype "passive"))
    )
    (net (code "86") (name "/五向开关-下") (class "Default")
      (node (ref "U8") (pin "63") (pinfunction "PC6/I2S2_MCK/TIM8_CH1/SDIO_D6/USART6_TX/DCMI_D0/TIM3_CH1/EVENTOUT_63") (pintype "bidirectional"))
      (node (ref "s1") (pin "4") (pinfunction "下_4") (pintype "passive"))
    )
    (net (code "87") (name "/五向开关-中") (class "Default")
      (node (ref "U8") (pin "65") (pinfunction "PC8/TIM8_CH3/SDIO_D0/TIM3_CH3/USART6_CK/DCMI_D2/EVENTOUT_65") (pintype "bidirectional"))
      (node (ref "s1") (pin "3") (pinfunction "中_3") (pintype "passive"))
    )
    (net (code "88") (name "/五向开关-右") (class "Default")
      (node (ref "U8") (pin "67") (pinfunction "PA8/MCO1/USART1_CK/TIM1_CH1/I2C3_SCL/OTG_FS_SOF/EVENTOUT_67") (pintype "bidirectional"))
      (node (ref "s1") (pin "5") (pinfunction "右_5") (pintype "passive"))
    )
    (net (code "89") (name "/五向开关-左") (class "Default")
      (node (ref "U8") (pin "64") (pinfunction "PC7/I2S3_MCK/TIM8_CH2/SDIO_D7/USART6_RX/DCMI_D1/TIM3_CH2/EVENTOUT_64") (pintype "bidirectional"))
      (node (ref "s1") (pin "2") (pinfunction "左_2") (pintype "passive"))
    )
    (net (code "90") (name "/电压输入1") (class "Default")
      (node (ref "C40") (pin "2") (pinfunction "2_2") (pintype "passive"))
      (node (ref "R52") (pin "1") (pinfunction "1_1") (pintype "passive"))
      (node (ref "R53") (pin "2") (pinfunction "2_2") (pintype "passive"))
      (node (ref "U8") (pin "29") (pinfunction "PA4/SPI1_NSS/SPI3_NSS/USART2_CK/DCMI_HSYNC/OTG_HS_SOF/I2S3_WS/EVENTOUT/ADC12_IN4/DAC1_OUT_29") (pintype "bidirectional"))
    )
    (net (code "91") (name "/电压输入2") (class "Default")
      (node (ref "C41") (pin "2") (pinfunction "2_2") (pintype "passive"))
      (node (ref "R54") (pin "1") (pinfunction "1_1") (pintype "passive"))
      (node (ref "R55") (pin "2") (pinfunction "2_2") (pintype "passive"))
      (node (ref "U8") (pin "30") (pinfunction "PA5/SPI1_SCK/OTG_HS_ULPI_CK/TIM2_CH1_ETR/TIM8_CHIN/EVENTOUT/ADC12_IN5/DAC2_OUT_30") (pintype "bidirectional"))
    )
    (net (code "92") (name "/编码器-按键") (class "Default")
      (node (ref "S2") (pin "4") (pinfunction "4_4") (pintype "passive"))
      (node (ref "U8") (pin "35") (pinfunction "PB0/TIM3_CH3/TIM8_CH2N/OTG_HS_ULPI_D1/ETH_MII_RXD2/TIM1_CH2N/EVENTOUT/ADC12_IN8_35") (pintype "bidirectional"))
    )
    (net (code "93") (name "/编码器A") (class "Default")
      (node (ref "S2") (pin "2") (pinfunction "2_2") (pintype "passive"))
      (node (ref "U8") (pin "33") (pinfunction "PC4/ETH_RMII_RX_D0/ETH_MII_RX_D0/EVENTOUT/ADC12_IN14_33") (pintype "bidirectional"))
    )
    (net (code "94") (name "/编码器B") (class "Default")
      (node (ref "S2") (pin "3") (pinfunction "3_3") (pintype "passive"))
      (node (ref "U8") (pin "34") (pinfunction "PC5/ETH_RMII_RX_D1/ETH_MII_RX_D1/EVENTOUT/ADC12_IN15_34") (pintype "bidirectional"))
    )
    (net (code "95") (name "/背光使能") (class "Default")
      (node (ref "P6") (pin "5") (pinfunction "5_5") (pintype "passive"))
      (node (ref "U8") (pin "31") (pinfunction "PA6/SPI1_MISO/TIM8_BKIN/TIM13_CH1/DCMI_PIXCLK/TIM3_CH1/TIM1_BKIN/EVENTOUT/ADC12_IN6_31") (pintype "bidirectional"))
    )
    (net (code "96") (name "/蜂鸣器") (class "Default")
      (node (ref "U16") (pin "6") (pinfunction "6B_6") (pintype "passive"))
      (node (ref "U8") (pin "89") (pinfunction "PB3(JTDO/TRACESWO)/JTDO/TRACESWO/SPI3_SCK/I2S3_CK/TIM2_CH2/SPI1_SCK/EVENTOUT_89") (pintype "bidirectional"))
    )
    (net (code "97") (name "3.3V") (class "Default")
      (node (ref "C10") (pin "1") (pinfunction "1_1") (pintype "passive"))
      (node (ref "C13") (pin "2") (pinfunction "2_2") (pintype "passive"))
      (node (ref "C14") (pin "2") (pinfunction "2_2") (pintype "passive"))
      (node (ref "C15") (pin "2") (pinfunction "2_2") (pintype "passive"))
      (node (ref "C16") (pin "2") (pinfunction "2_2") (pintype "passive"))
      (node (ref "C44") (pin "2") (pinfunction "2_2") (pintype "passive"))
      (node (ref "C45") (pin "2") (pinfunction "2_2") (pintype "passive"))
      (node (ref "C46") (pin "2") (pinfunction "2_2") (pintype "passive"))
      (node (ref "C47") (pin "2") (pinfunction "2_2") (pintype "passive"))
      (node (ref "C9") (pin "1") (pinfunction "1_1") (pintype "passive"))
      (node (ref "D5") (pin "1") (pinfunction "A_1") (pintype "passive"))
      (node (ref "M1") (pin "12") (pinfunction "VCC_12") (pintype "passive"))
      (node (ref "P6") (pin "1") (pinfunction "1_1") (pintype "passive"))
      (node (ref "P6") (pin "2") (pinfunction "2_2") (pintype "passive"))
      (node (ref "P7") (pin "1") (pinfunction "1_1") (pintype "passive"))
      (node (ref "R19") (pin "2") (pinfunction "2_2") (pintype "passive"))
      (node (ref "R21") (pin "2") (pinfunction "2_2") (pintype "passive"))
      (node (ref "R3") (pin "2") (pinfunction "2_2") (pintype "passive"))
      (node (ref "U11") (pin "5") (pinfunction "Vio_5") (pintype "passive"))
      (node (ref "U3") (pin "2") (pinfunction "VOUT_2") (pintype "passive"))
      (node (ref "U8") (pin "100") (pinfunction "VDD_100") (pintype "power_in"))
      (node (ref "U8") (pin "11") (pinfunction "VDD_11") (pintype "power_in"))
      (node (ref "U8") (pin "19") (pinfunction "VDD_19") (pintype "power_in"))
      (node (ref "U8") (pin "28") (pinfunction "VDD_28") (pintype "power_in"))
      (node (ref "U8") (pin "50") (pinfunction "VDD_50") (pintype "power_in"))
      (node (ref "U8") (pin "6") (pinfunction "VBAT_6") (pintype "power_in"))
      (node (ref "U8") (pin "75") (pinfunction "VDD_75") (pintype "power_in"))
      (node (ref "U9") (pin "8") (pinfunction "VCC_8") (pintype "passive"))
    )
    (net (code "98") (name "5V") (class "Default")
      (node (ref "C1") (pin "2") (pinfunction "2_2") (pintype "passive"))
      (node (ref "C11") (pin "2") (pinfunction "2_2") (pintype "passive"))
      (node (ref "C12") (pin "2") (pinfunction "2_2") (pintype "passive"))
      (node (ref "C42") (pin "2") (pinfunction "2_2") (pintype "passive"))
      (node (ref "C7") (pin "1") (pinfunction "1_1") (pintype "passive"))
      (node (ref "C8") (pin "2") (pinfunction "2_2") (pintype "passive"))
      (node (ref "D12") (pin "2") (pinfunction "K_2") (pintype "passive"))
      (node (ref "D3") (pin "2") (pinfunction "K_2") (pintype "passive"))
      (node (ref "I2") (pin "2") (pinfunction "2_2") (pintype "passive"))
      (node (ref "I3") (pin "2") (pinfunction "2_2") (pintype "passive"))
      (node (ref "LS1") (pin "1") (pinfunction "A_1") (pintype "passive"))
      (node (ref "R7") (pin "1") (pinfunction "1_1") (pintype "passive"))
      (node (ref "U1") (pin "1") (pinfunction "VDD_1") (pintype "passive"))
      (node (ref "U11") (pin "3") (pinfunction "VCC_3") (pintype "passive"))
      (node (ref "U3") (pin "3") (pinfunction "VIN_3") (pintype "passive"))
    )
    (net (code "99") (name "24V") (class "Default")
      (node (ref "C4") (pin "1") (pinfunction "1_1") (pintype "passive"))
      (node (ref "C48") (pin "2") (pinfunction "2_2") (pintype "passive"))
      (node (ref "C49") (pin "2") (pinfunction "2_2") (pintype "passive"))
      (node (ref "C5") (pin "2") (pinfunction "2_2") (pintype "passive"))
      (node (ref "C50") (pin "2") (pinfunction "2_2") (pintype "passive"))
      (node (ref "C51") (pin "2") (pinfunction "2_2") (pintype "passive"))
      (node (ref "C52") (pin "2") (pinfunction "2_2") (pintype "passive"))
      (node (ref "C53") (pin "2") (pinfunction "2_2") (pintype "passive"))
      (node (ref "D1") (pin "2") (pinfunction "K_2") (pintype "passive"))
      (node (ref "D2") (pin "2") (pinfunction "K_2") (pintype "passive"))
      (node (ref "I4") (pin "1") (pinfunction "1_1") (pintype "passive"))
      (node (ref "K1") (pin "2") (pinfunction "2_2") (pintype "passive"))
      (node (ref "K2") (pin "1") (pinfunction "1_1") (pintype "passive"))
      (node (ref "K3") (pin "1") (pinfunction "1_1") (pintype "passive"))
      (node (ref "K4") (pin "1") (pinfunction "1_1") (pintype "passive"))
      (node (ref "K5") (pin "1") (pinfunction "1_1") (pintype "passive"))
      (node (ref "R6") (pin "1") (pinfunction "1_1") (pintype "passive"))
      (node (ref "U10") (pin "1") (pinfunction "VSP_1") (pintype "passive"))
      (node (ref "U12") (pin "1") (pinfunction "VSP_1") (pintype "passive"))
      (node (ref "U14") (pin "1") (pinfunction "VSP_1") (pintype "passive"))
      (node (ref "U15") (pin "1") (pinfunction "VSP_1") (pintype "passive"))
      (node (ref "U16") (pin "9") (pinfunction "COM_9") (pintype "passive"))
      (node (ref "U2") (pin "2") (pinfunction "VIN_2") (pintype "passive"))
      (node (ref "U7") (pin "9") (pinfunction "COM_9") (pintype "passive"))
    )
    (net (code "100") (name "A3.3V") (class "Default")
      (node (ref "C24") (pin "2") (pinfunction "2_2") (pintype "passive"))
      (node (ref "C25") (pin "2") (pinfunction "2_2") (pintype "passive"))
      (node (ref "C43") (pin "2") (pinfunction "2_2") (pintype "passive"))
      (node (ref "U5") (pin "2") (pinfunction "VOUT_2") (pintype "passive"))
      (node (ref "U8") (pin "21") (pinfunction "VREF+_21") (pintype "power_in"))
      (node (ref "U8") (pin "22") (pinfunction "VDDA_22") (pintype "power_in"))
    )
    (net (code "101") (name "A12V") (class "Default")
      (node (ref "C19") (pin "1") (pinfunction "1_1") (pintype "passive"))
      (node (ref "C21") (pin "2") (pinfunction "2_2") (pintype "passive"))
      (node (ref "U13") (pin "18") (pinfunction "VDD_18") (pintype "passive"))
      (node (ref "U4") (pin "3") (pinfunction "OUT_3") (pintype "passive"))
    )
    (net (code "102") (name "A24V") (class "Default")
      (node (ref "C18") (pin "1") (pinfunction "1_1") (pintype "passive"))
      (node (ref "C20") (pin "2") (pinfunction "2_2") (pintype "passive"))
      (node (ref "I4") (pin "2") (pinfunction "2_2") (pintype "passive"))
      (node (ref "R10") (pin "2") (pinfunction "2_2") (pintype "passive"))
      (node (ref "R12") (pin "2") (pinfunction "2_2") (pintype "passive"))
      (node (ref "R13") (pin "2") (pinfunction "2_2") (pintype "passive"))
      (node (ref "U4") (pin "1") (pinfunction "IN_1") (pintype "passive"))
    )
    (net (code "103") (name "AGND") (class "Default")
      (node (ref "C18") (pin "2") (pinfunction "2_2") (pintype "passive"))
      (node (ref "C19") (pin "2") (pinfunction "2_2") (pintype "passive"))
      (node (ref "C20") (pin "1") (pinfunction "1_1") (pintype "passive"))
      (node (ref "C21") (pin "1") (pinfunction "1_1") (pintype "passive"))
      (node (ref "C22") (pin "1") (pinfunction "1_1") (pintype "passive"))
      (node (ref "C23") (pin "1") (pinfunction "1_1") (pintype "passive"))
      (node (ref "C24") (pin "1") (pinfunction "1_1") (pintype "passive"))
      (node (ref "C25") (pin "1") (pinfunction "1_1") (pintype "passive"))
      (node (ref "C26") (pin "2") (pinfunction "2_2") (pintype "passive"))
      (node (ref "C36") (pin "1") (pinfunction "1_1") (pintype "passive"))
      (node (ref "C37") (pin "1") (pinfunction "1_1") (pintype "passive"))
      (node (ref "C38") (pin "1") (pinfunction "1_1") (pintype "passive"))
      (node (ref "C39") (pin "1") (pinfunction "1_1") (pintype "passive"))
      (node (ref "C40") (pin "1") (pinfunction "1_1") (pintype "passive"))
      (node (ref "C41") (pin "1") (pinfunction "1_1") (pintype "passive"))
      (node (ref "C43") (pin "1") (pinfunction "1_1") (pintype "passive"))
      (node (ref "C48") (pin "1") (pinfunction "1_1") (pintype "passive"))
      (node (ref "C49") (pin "1") (pinfunction "1_1") (pintype "passive"))
      (node (ref "C50") (pin "1") (pinfunction "1_1") (pintype "passive"))
      (node (ref "C51") (pin "1") (pinfunction "1_1") (pintype "passive"))
      (node (ref "D10") (pin "1") (pinfunction "A_1") (pintype "passive"))
      (node (ref "D11") (pin "1") (pinfunction "A_1") (pintype "passive"))
      (node (ref "P8") (pin "2") (pinfunction "2_2") (pintype "passive"))
      (node (ref "P8") (pin "5") (pinfunction "5_5") (pintype "passive"))
      (node (ref "P8") (pin "8") (pinfunction "8_8") (pintype "passive"))
      (node (ref "R16") (pin "1") (pinfunction "1_1") (pintype "passive"))
      (node (ref "R34") (pin "2") (pinfunction "2_2") (pintype "passive"))
      (node (ref "R36") (pin "2") (pinfunction "2_2") (pintype "passive"))
      (node (ref "R39") (pin "2") (pinfunction "2_2") (pintype "passive"))
      (node (ref "R41") (pin "2") (pinfunction "2_2") (pintype "passive"))
      (node (ref "R44") (pin "2") (pinfunction "2_2") (pintype "passive"))
      (node (ref "R46") (pin "2") (pinfunction "2_2") (pintype "passive"))
      (node (ref "R49") (pin "2") (pinfunction "2_2") (pintype "passive"))
      (node (ref "R51") (pin "2") (pinfunction "2_2") (pintype "passive"))
      (node (ref "R53") (pin "1") (pinfunction "1_1") (pintype "passive"))
      (node (ref "R55") (pin "1") (pinfunction "1_1") (pintype "passive"))
      (node (ref "R9") (pin "2") (pinfunction "2_2") (pintype "passive"))
      (node (ref "U10") (pin "10") (pinfunction "GND_10") (pintype "passive"))
      (node (ref "U10") (pin "11") (pinfunction "GND(PAD)_11") (pintype "passive"))
      (node (ref "U12") (pin "10") (pinfunction "GND_10") (pintype "passive"))
      (node (ref "U12") (pin "11") (pinfunction "GND(PAD)_11") (pintype "passive"))
      (node (ref "U13") (pin "3") (pinfunction "Vss_3") (pintype "passive"))
      (node (ref "U13") (pin "5") (pinfunction "AGND_5") (pintype "passive"))
      (node (ref "U14") (pin "10") (pinfunction "GND_10") (pintype "passive"))
      (node (ref "U14") (pin "11") (pinfunction "GND(PAD)_11") (pintype "passive"))
      (node (ref "U15") (pin "10") (pinfunction "GND_10") (pintype "passive"))
      (node (ref "U15") (pin "11") (pinfunction "GND(PAD)_11") (pintype "passive"))
      (node (ref "U4") (pin "2") (pinfunction "GND_2") (pintype "passive"))
      (node (ref "U5") (pin "1") (pinfunction "VSS_1") (pintype "passive"))
      (node (ref "U6") (pin "3") (pinfunction "A_3") (pintype "passive"))
      (node (ref "U8") (pin "20") (pinfunction "VSSA_20") (pintype "power_in"))
    )
    (net (code "104") (name "GND") (class "Default")
      (node (ref "C1") (pin "1") (pinfunction "1_1") (pintype "passive"))
      (node (ref "C10") (pin "2") (pinfunction "2_2") (pintype "passive"))
      (node (ref "C12") (pin "1") (pinfunction "1_1") (pintype "passive"))
      (node (ref "C13") (pin "1") (pinfunction "1_1") (pintype "passive"))
      (node (ref "C14") (pin "1") (pinfunction "1_1") (pintype "passive"))
      (node (ref "C15") (pin "1") (pinfunction "1_1") (pintype "passive"))
      (node (ref "C16") (pin "1") (pinfunction "1_1") (pintype "passive"))
      (node (ref "C17") (pin "1") (pinfunction "1_1") (pintype "passive"))
      (node (ref "C2") (pin "1") (pinfunction "1_1") (pintype "passive"))
      (node (ref "C27") (pin "1") (pinfunction "1_1") (pintype "passive"))
      (node (ref "C28") (pin "1") (pinfunction "1_1") (pintype "passive"))
      (node (ref "C29") (pin "1") (pinfunction "1_1") (pintype "passive"))
      (node (ref "C3") (pin "2") (pinfunction "2_2") (pintype "passive"))
      (node (ref "C30") (pin "1") (pinfunction "1_1") (pintype "passive"))
      (node (ref "C31") (pin "1") (pinfunction "1_1") (pintype "passive"))
      (node (ref "C32") (pin "1") (pinfunction "1_1") (pintype "passive"))
      (node (ref "C33") (pin "1") (pinfunction "1_1") (pintype "passive"))
      (node (ref "C34") (pin "1") (pinfunction "1_1") (pintype "passive"))
      (node (ref "C35") (pin "1") (pinfunction "1_1") (pintype "passive"))
      (node (ref "C4") (pin "2") (pinfunction "2_2") (pintype "passive"))
      (node (ref "C42") (pin "1") (pinfunction "1_1") (pintype "passive"))
      (node (ref "C44") (pin "1") (pinfunction "1_1") (pintype "passive"))
      (node (ref "C45") (pin "1") (pinfunction "1_1") (pintype "passive"))
      (node (ref "C46") (pin "1") (pinfunction "1_1") (pintype "passive"))
      (node (ref "C47") (pin "1") (pinfunction "1_1") (pintype "passive"))
      (node (ref "C5") (pin "1") (pinfunction "1_1") (pintype "passive"))
      (node (ref "C52") (pin "1") (pinfunction "1_1") (pintype "passive"))
      (node (ref "C53") (pin "1") (pinfunction "1_1") (pintype "passive"))
      (node (ref "C7") (pin "2") (pinfunction "2_2") (pintype "passive"))
      (node (ref "C8") (pin "1") (pinfunction "1_1") (pintype "passive"))
      (node (ref "C9") (pin "2") (pinfunction "2_2") (pintype "passive"))
      (node (ref "D2") (pin "1") (pinfunction "A_1") (pintype "passive"))
      (node (ref "D3") (pin "1") (pinfunction "A_1") (pintype "passive"))
      (node (ref "D4") (pin "1") (pinfunction "A_1") (pintype "passive"))
      (node (ref "D6") (pin "1") (pinfunction "A_1") (pintype "passive"))
      (node (ref "D7") (pin "1") (pinfunction "A_1") (pintype "passive"))
      (node (ref "D8") (pin "1") (pinfunction "A_1") (pintype "passive"))
      (node (ref "D9") (pin "1") (pinfunction "A_1") (pintype "passive"))
      (node (ref "M1") (pin "1") (pinfunction "GND_1") (pintype "passive"))
      (node (ref "P3") (pin "2") (pinfunction "2_2") (pintype "passive"))
      (node (ref "P3") (pin "3") (pinfunction "NC_3") (pintype "passive"))
      (node (ref "P4") (pin "2") (pinfunction "2_2") (pintype "passive"))
      (node (ref "P5") (pin "2") (pinfunction "2_2") (pintype "passive"))
      (node (ref "P5") (pin "5") (pinfunction "5_5") (pintype "passive"))
      (node (ref "P5") (pin "8") (pinfunction "8_8") (pintype "passive"))
      (node (ref "P6") (pin "27") (pinfunction "27_27") (pintype "passive"))
      (node (ref "P6") (pin "28") (pinfunction "28_28") (pintype "passive"))
      (node (ref "P6") (pin "3") (pinfunction "3_3") (pintype "passive"))
      (node (ref "P6") (pin "4") (pinfunction "4_4") (pintype "passive"))
      (node (ref "P7") (pin "3") (pinfunction "3_3") (pintype "passive"))
      (node (ref "P9") (pin "5") (pinfunction "GND_5") (pintype "passive"))
      (node (ref "P9") (pin "6") (pinfunction "外壳_6") (pintype "passive"))
      (node (ref "Q1") (pin "2") (pinfunction "S_2") (pintype "passive"))
      (node (ref "R18") (pin "1") (pinfunction "1_1") (pintype "passive"))
      (node (ref "R23") (pin "2") (pinfunction "2_2") (pintype "passive"))
      (node (ref "R25") (pin "2") (pinfunction "2_2") (pintype "passive"))
      (node (ref "R29") (pin "1") (pinfunction "1_1") (pintype "passive"))
      (node (ref "R8") (pin "2") (pinfunction "2_2") (pintype "passive"))
      (node (ref "R9") (pin "1") (pinfunction "1_1") (pintype "passive"))
      (node (ref "S2") (pin "1") (pinfunction "1_1") (pintype "passive"))
      (node (ref "S2") (pin "5") (pinfunction "5_5") (pintype "passive"))
      (node (ref "S2") (pin "6") (pinfunction "6_6") (pintype "passive"))
      (node (ref "U1") (pin "5") (pinfunction "GND_5") (pintype "passive"))
      (node (ref "U11") (pin "2") (pinfunction "GND_2") (pintype "passive"))
      (node (ref "U11") (pin "8") (pinfunction "S_8") (pintype "passive"))
      (node (ref "U13") (pin "6") (pinfunction "DGND_6") (pintype "passive"))
      (node (ref "U16") (pin "8") (pinfunction "E_8") (pintype "passive"))
      (node (ref "U2") (pin "4") (pinfunction "GND_4") (pintype "passive"))
      (node (ref "U2") (pin "9") (pinfunction "GND_9") (pintype "passive"))
      (node (ref "U3") (pin "1") (pinfunction "VSS_1") (pintype "passive"))
      (node (ref "U7") (pin "8") (pinfunction "E_8") (pintype "passive"))
      (node (ref "U8") (pin "10") (pinfunction "VSS_10") (pintype "power_in"))
      (node (ref "U8") (pin "27") (pinfunction "VSS_27") (pintype "power_in"))
      (node (ref "U8") (pin "74") (pinfunction "VSS_74") (pintype "power_in"))
      (node (ref "U8") (pin "99") (pinfunction "VSS_99") (pintype "power_in"))
      (node (ref "U9") (pin "5") (pinfunction "GND_5") (pintype "passive"))
      (node (ref "s1") (pin "1") (pinfunction "Common_1") (pintype "passive"))
    )
    (net (code "105") (name "Net-(C35-Pad2)") (class "Default")
      (node (ref "C35") (pin "2") (pinfunction "2_2") (pintype "passive"))
      (node (ref "R31") (pin "1") (pinfunction "1_1") (pintype "passive"))
      (node (ref "R33") (pin "2") (pinfunction "2_2") (pintype "passive"))
    )
    (net (code "106") (name "Net-(D1-A)") (class "Default")
      (node (ref "D1") (pin "1") (pinfunction "A_1") (pintype "passive"))
      (node (ref "F2") (pin "2") (pinfunction "2_2") (pintype "passive"))
    )
    (net (code "107") (name "Net-(D4-K)") (class "Default")
      (node (ref "D4") (pin "2") (pinfunction "K_2") (pintype "passive"))
      (node (ref "P4") (pin "1") (pinfunction "1_1") (pintype "passive"))
      (node (ref "R17") (pin "2") (pinfunction "2_2") (pintype "passive"))
    )
    (net (code "108") (name "Net-(D5-K)") (class "Default")
      (node (ref "D5") (pin "2") (pinfunction "K_2") (pintype "passive"))
      (node (ref "R24") (pin "1") (pinfunction "1_1") (pintype "passive"))
    )
    (net (code "109") (name "Net-(D12-A)") (class "Default")
      (node (ref "D12") (pin "1") (pinfunction "A_1") (pintype "passive"))
      (node (ref "P9") (pin "1") (pinfunction "5V_1") (pintype "passive"))
    )
    (net (code "110") (name "Net-(F1-Pad2)") (class "Default")
      (node (ref "F1") (pin "2") (pinfunction "2_2") (pintype "passive"))
      (node (ref "K1") (pin "4") (pinfunction "4_4") (pintype "passive"))
    )
    (net (code "111") (name "Net-(F2-Pad1)") (class "Default")
      (node (ref "F2") (pin "1") (pinfunction "1_1") (pintype "passive"))
      (node (ref "P3") (pin "1") (pinfunction "1_1") (pintype "passive"))
    )
    (net (code "112") (name "Net-(I1-Pad1)") (class "Default")
      (node (ref "I1") (pin "1") (pinfunction "1_1") (pintype "passive"))
      (node (ref "K1") (pin "3") (pinfunction "3_3") (pintype "passive"))
    )
    (net (code "113") (name "Net-(I1-Pad2)") (class "Default")
      (node (ref "I1") (pin "2") (pinfunction "2_2") (pintype "passive"))
      (node (ref "P2") (pin "1") (pinfunction "1_1") (pintype "passive"))
    )
    (net (code "114") (name "Net-(I1-Pad3)") (class "Default")
      (node (ref "I1") (pin "3") (pinfunction "3_3") (pintype "passive"))
      (node (ref "R2") (pin "1") (pinfunction "1_1") (pintype "passive"))
    )
    (net (code "115") (name "Net-(I1-Pad4)") (class "Default")
      (node (ref "I1") (pin "4") (pinfunction "4_4") (pintype "passive"))
      (node (ref "R4") (pin "2") (pinfunction "2_2") (pintype "passive"))
      (node (ref "R5") (pin "1") (pinfunction "1_1") (pintype "passive"))
    )
    (net (code "116") (name "Net-(LS1-B)") (class "Default")
      (node (ref "LS1") (pin "2") (pinfunction "B_2") (pintype "passive"))
      (node (ref "U16") (pin "11") (pinfunction "6C_11") (pintype "passive"))
    )
    (net (code "117") (name "Net-(Q1-G)") (class "Default")
      (node (ref "Q1") (pin "1") (pinfunction "G_1") (pintype "passive"))
      (node (ref "U1") (pin "7") (pinfunction "CF1_7") (pintype "passive"))
    )
    (net (code "118") (name "Net-(Q2-B)") (class "Default")
      (node (ref "Q2") (pin "1") (pinfunction "B_1") (pintype "passive"))
      (node (ref "Q3") (pin "3") (pinfunction "S_3") (pintype "passive"))
      (node (ref "R30") (pin "2") (pinfunction "2_2") (pintype "passive"))
    )
    (net (code "119") (name "Net-(Q2-C)") (class "Default")
      (node (ref "Q2") (pin "3") (pinfunction "C_3") (pintype "passive"))
      (node (ref "Q3") (pin "1") (pinfunction "G_1") (pintype "passive"))
      (node (ref "U10") (pin "3") (pinfunction "VG_3") (pintype "passive"))
    )
    (net (code "120") (name "Net-(Q2-E)") (class "Default")
      (node (ref "Q2") (pin "2") (pinfunction "E_2") (pintype "passive"))
      (node (ref "R30") (pin "1") (pinfunction "1_1") (pintype "passive"))
      (node (ref "U10") (pin "2") (pinfunction "IS_2") (pintype "passive"))
    )
    (net (code "121") (name "Net-(Q3-D)") (class "Default")
      (node (ref "C36") (pin "2") (pinfunction "2_2") (pintype "passive"))
      (node (ref "Q3") (pin "2") (pinfunction "D_2") (pintype "passive"))
      (node (ref "R32") (pin "1") (pinfunction "1_1") (pintype "passive"))
    )
    (net (code "122") (name "Net-(Q4-B)") (class "Default")
      (node (ref "Q4") (pin "1") (pinfunction "B_1") (pintype "passive"))
      (node (ref "Q5") (pin "3") (pinfunction "S_3") (pintype "passive"))
      (node (ref "R37") (pin "2") (pinfunction "2_2") (pintype "passive"))
    )
    (net (code "123") (name "Net-(Q4-C)") (class "Default")
      (node (ref "Q4") (pin "3") (pinfunction "C_3") (pintype "passive"))
      (node (ref "Q5") (pin "1") (pinfunction "G_1") (pintype "passive"))
      (node (ref "U12") (pin "3") (pinfunction "VG_3") (pintype "passive"))
    )
    (net (code "124") (name "Net-(Q4-E)") (class "Default")
      (node (ref "Q4") (pin "2") (pinfunction "E_2") (pintype "passive"))
      (node (ref "R37") (pin "1") (pinfunction "1_1") (pintype "passive"))
      (node (ref "U12") (pin "2") (pinfunction "IS_2") (pintype "passive"))
    )
    (net (code "125") (name "Net-(Q5-D)") (class "Default")
      (node (ref "C37") (pin "2") (pinfunction "2_2") (pintype "passive"))
      (node (ref "Q5") (pin "2") (pinfunction "D_2") (pintype "passive"))
      (node (ref "R38") (pin "1") (pinfunction "1_1") (pintype "passive"))
    )
    (net (code "126") (name "Net-(Q7-B)") (class "Default")
      (node (ref "Q7") (pin "1") (pinfunction "B_1") (pintype "passive"))
      (node (ref "Q8") (pin "3") (pinfunction "S_3") (pintype "passive"))
      (node (ref "R42") (pin "2") (pinfunction "2_2") (pintype "passive"))
    )
    (net (code "127") (name "Net-(Q7-C)") (class "Default")
      (node (ref "Q7") (pin "3") (pinfunction "C_3") (pintype "passive"))
      (node (ref "Q8") (pin "1") (pinfunction "G_1") (pintype "passive"))
      (node (ref "U14") (pin "3") (pinfunction "VG_3") (pintype "passive"))
    )
    (net (code "128") (name "Net-(Q7-E)") (class "Default")
      (node (ref "Q7") (pin "2") (pinfunction "E_2") (pintype "passive"))
      (node (ref "R42") (pin "1") (pinfunction "1_1") (pintype "passive"))
      (node (ref "U14") (pin "2") (pinfunction "IS_2") (pintype "passive"))
    )
    (net (code "129") (name "Net-(Q8-D)") (class "Default")
      (node (ref "C38") (pin "2") (pinfunction "2_2") (pintype "passive"))
      (node (ref "Q8") (pin "2") (pinfunction "D_2") (pintype "passive"))
      (node (ref "R43") (pin "1") (pinfunction "1_1") (pintype "passive"))
    )
    (net (code "130") (name "Net-(Q9-E)") (class "Default")
      (node (ref "Q9") (pin "2") (pinfunction "E_2") (pintype "passive"))
      (node (ref "R47") (pin "1") (pinfunction "1_1") (pintype "passive"))
      (node (ref "U15") (pin "2") (pinfunction "IS_2") (pintype "passive"))
    )
    (net (code "131") (name "Net-(Q10-D)") (class "Default")
      (node (ref "C39") (pin "2") (pinfunction "2_2") (pintype "passive"))
      (node (ref "Q10") (pin "2") (pinfunction "D_2") (pintype "passive"))
      (node (ref "R48") (pin "1") (pinfunction "1_1") (pintype "passive"))
    )
    (net (code "132") (name "Net-(Q10-G)") (class "Default")
      (node (ref "Q10") (pin "1") (pinfunction "G_1") (pintype "passive"))
      (node (ref "Q9") (pin "3") (pinfunction "C_3") (pintype "passive"))
      (node (ref "U15") (pin "3") (pinfunction "VG_3") (pintype "passive"))
    )
    (net (code "133") (name "Net-(Q10-S)") (class "Default")
      (node (ref "Q10") (pin "3") (pinfunction "S_3") (pintype "passive"))
      (node (ref "Q9") (pin "1") (pinfunction "B_1") (pintype "passive"))
      (node (ref "R47") (pin "2") (pinfunction "2_2") (pintype "passive"))
    )
    (net (code "134") (name "Net-(R1-Pad1)") (class "Default")
      (node (ref "R1") (pin "1") (pinfunction "1_1") (pintype "passive"))
      (node (ref "R2") (pin "2") (pinfunction "2_2") (pintype "passive"))
      (node (ref "R4") (pin "1") (pinfunction "1_1") (pintype "passive"))
    )
    (net (code "135") (name "Net-(R11-Pad1)") (class "Default")
      (node (ref "R11") (pin "1") (pinfunction "1_1") (pintype "passive"))
      (node (ref "R14") (pin "2") (pinfunction "2_2") (pintype "passive"))
      (node (ref "R15") (pin "2") (pinfunction "2_2") (pintype "passive"))
    )
    (net (code "136") (name "Net-(R35-Pad2)") (class "Default")
      (node (ref "R35") (pin "2") (pinfunction "2_2") (pintype "passive"))
      (node (ref "R36") (pin "1") (pinfunction "1_1") (pintype "passive"))
    )
    (net (code "137") (name "Net-(R40-Pad2)") (class "Default")
      (node (ref "R40") (pin "2") (pinfunction "2_2") (pintype "passive"))
      (node (ref "R41") (pin "1") (pinfunction "1_1") (pintype "passive"))
    )
    (net (code "138") (name "Net-(R45-Pad2)") (class "Default")
      (node (ref "R45") (pin "2") (pinfunction "2_2") (pintype "passive"))
      (node (ref "R46") (pin "1") (pinfunction "1_1") (pintype "passive"))
    )
    (net (code "139") (name "Net-(R50-Pad2)") (class "Default")
      (node (ref "R50") (pin "2") (pinfunction "2_2") (pintype "passive"))
      (node (ref "R51") (pin "1") (pinfunction "1_1") (pintype "passive"))
    )
    (net (code "140") (name "Net-(U1-VIN)") (class "Default")
      (node (ref "C2") (pin "2") (pinfunction "2_2") (pintype "passive"))
      (node (ref "R1") (pin "2") (pinfunction "2_2") (pintype "passive"))
      (node (ref "U1") (pin "3") (pinfunction "VIN_3") (pintype "passive"))
    )
    (net (code "141") (name "Net-(U1-VIP)") (class "Default")
      (node (ref "C3") (pin "1") (pinfunction "1_1") (pintype "passive"))
      (node (ref "R5") (pin "2") (pinfunction "2_2") (pintype "passive"))
      (node (ref "U1") (pin "2") (pinfunction "VIP_2") (pintype "passive"))
    )
    (net (code "142") (name "Net-(U2-BST)") (class "Default")
      (node (ref "C6") (pin "2") (pinfunction "2_2") (pintype "passive"))
      (node (ref "U2") (pin "1") (pinfunction "BST_1") (pintype "passive"))
    )
    (net (code "143") (name "Net-(U2-FB)") (class "Default")
      (node (ref "C11") (pin "1") (pinfunction "1_1") (pintype "passive"))
      (node (ref "R7") (pin "2") (pinfunction "2_2") (pintype "passive"))
      (node (ref "R8") (pin "1") (pinfunction "1_1") (pintype "passive"))
      (node (ref "U2") (pin "5") (pinfunction "FB_5") (pintype "passive"))
    )
    (net (code "144") (name "Net-(U2-LX)") (class "Default")
      (node (ref "C6") (pin "1") (pinfunction "1_1") (pintype "passive"))
      (node (ref "I2") (pin "1") (pinfunction "1_1") (pintype "passive"))
      (node (ref "U2") (pin "3") (pinfunction "LX_3") (pintype "passive"))
    )
    (net (code "145") (name "Net-(U2-SS)") (class "Default")
      (node (ref "C17") (pin "2") (pinfunction "2_2") (pintype "passive"))
      (node (ref "U2") (pin "8") (pinfunction "SS_8") (pintype "passive"))
    )
    (net (code "146") (name "Net-(U2-~{SHDN})") (class "Default")
      (node (ref "R6") (pin "2") (pinfunction "2_2") (pintype "passive"))
      (node (ref "U2") (pin "7") (pinfunction "~{SHDN}_7") (pintype "passive"))
    )
    (net (code "147") (name "Net-(U5-VIN)") (class "Default")
      (node (ref "C22") (pin "2") (pinfunction "2_2") (pintype "passive"))
      (node (ref "C23") (pin "2") (pinfunction "2_2") (pintype "passive"))
      (node (ref "I3") (pin "1") (pinfunction "1_1") (pintype "passive"))
      (node (ref "U5") (pin "3") (pinfunction "VIN_3") (pintype "passive"))
    )
    (net (code "148") (name "Net-(U6-REF)") (class "Default")
      (node (ref "R14") (pin "1") (pinfunction "1_1") (pintype "passive"))
      (node (ref "R15") (pin "1") (pinfunction "1_1") (pintype "passive"))
      (node (ref "R16") (pin "2") (pinfunction "2_2") (pintype "passive"))
      (node (ref "U6") (pin "1") (pinfunction "REF_1") (pintype "passive"))
    )
    (net (code "149") (name "Net-(U7-4C)") (class "Default")
      (node (ref "K5") (pin "2") (pinfunction "2_2") (pintype "passive"))
      (node (ref "U7") (pin "13") (pinfunction "4C_13") (pintype "passive"))
    )
    (net (code "150") (name "Net-(U7-5C)") (class "Default")
      (node (ref "K4") (pin "2") (pinfunction "2_2") (pintype "passive"))
      (node (ref "U7") (pin "12") (pinfunction "5C_12") (pintype "passive"))
    )
    (net (code "151") (name "Net-(U7-6C)") (class "Default")
      (node (ref "K3") (pin "2") (pinfunction "2_2") (pintype "passive"))
      (node (ref "U7") (pin "11") (pinfunction "6C_11") (pintype "passive"))
    )
    (net (code "152") (name "Net-(U7-7C)") (class "Default")
      (node (ref "K2") (pin "2") (pinfunction "2_2") (pintype "passive"))
      (node (ref "U7") (pin "10") (pinfunction "7C_10") (pintype "passive"))
    )
    (net (code "153") (name "Net-(U8-BOOT0{slash}VPP)") (class "Default")
      (node (ref "R23") (pin "1") (pinfunction "1_1") (pintype "passive"))
      (node (ref "U8") (pin "94") (pinfunction "BOOT0/VPP_94") (pintype "input"))
    )
    (net (code "154") (name "Net-(U8-PB2-BOOT1(PB2){slash}EVENTOUT)") (class "Default")
      (node (ref "R25") (pin "1") (pinfunction "1_1") (pintype "passive"))
      (node (ref "U8") (pin "37") (pinfunction "PB2-BOOT1(PB2)/EVENTOUT_37") (pintype "bidirectional"))
    )
    (net (code "155") (name "Net-(U8-PH0-OSC_IN(PH0){slash}EVENTOUT{slash}OSC_IN)") (class "Default")
      (node (ref "C32") (pin "2") (pinfunction "2_2") (pintype "passive"))
      (node (ref "U8") (pin "12") (pinfunction "PH0-OSC_IN(PH0)/EVENTOUT/OSC_IN_12") (pintype "bidirectional"))
      (node (ref "Y1") (pin "2") (pinfunction "OSC2_2") (pintype "passive"))
    )
    (net (code "156") (name "Net-(U8-PH1-OSC_OUT(PH1){slash}EVENTOUT{slash}OSC_OUT)") (class "Default")
      (node (ref "C33") (pin "2") (pinfunction "2_2") (pintype "passive"))
      (node (ref "U8") (pin "13") (pinfunction "PH1-OSC_OUT(PH1)/EVENTOUT/OSC_OUT_13") (pintype "bidirectional"))
      (node (ref "Y1") (pin "1") (pinfunction "OSC1_1") (pintype "passive"))
    )
    (net (code "157") (name "Net-(U8-VCAP_1)") (class "Default")
      (node (ref "C29") (pin "2") (pinfunction "2_2") (pintype "passive"))
      (node (ref "U8") (pin "49") (pinfunction "VCAP_1_49") (pintype "power_in"))
    )
    (net (code "158") (name "Net-(U8-VCAP_2)") (class "Default")
      (node (ref "C30") (pin "2") (pinfunction "2_2") (pintype "passive"))
      (node (ref "U8") (pin "73") (pinfunction "VCAP_2_73") (pintype "power_in"))
    )
    (net (code "159") (name "Net-(U9-A)") (class "Default")
      (node (ref "R26") (pin "2") (pinfunction "2_2") (pintype "passive"))
      (node (ref "U9") (pin "6") (pinfunction "A_6") (pintype "passive"))
    )
    (net (code "160") (name "Net-(U9-B)") (class "Default")
      (node (ref "R28") (pin "2") (pinfunction "2_2") (pintype "passive"))
      (node (ref "U9") (pin "7") (pinfunction "B_7") (pintype "passive"))
    )
    (net (code "161") (name "Net-(U10-OD)") (class "Default")
      (node (ref "R34") (pin "1") (pinfunction "1_1") (pintype "passive"))
      (node (ref "U10") (pin "9") (pinfunction "OD_9") (pintype "passive"))
    )
    (net (code "162") (name "Net-(U10-SET)") (class "Default")
      (node (ref "K2") (pin "3") (pinfunction "3_3") (pintype "passive"))
      (node (ref "R35") (pin "1") (pinfunction "1_1") (pintype "passive"))
      (node (ref "U10") (pin "7") (pinfunction "SET_7") (pintype "passive"))
    )
    (net (code "163") (name "Net-(U12-OD)") (class "Default")
      (node (ref "R39") (pin "1") (pinfunction "1_1") (pintype "passive"))
      (node (ref "U12") (pin "9") (pinfunction "OD_9") (pintype "passive"))
    )
    (net (code "164") (name "Net-(U12-SET)") (class "Default")
      (node (ref "K3") (pin "3") (pinfunction "3_3") (pintype "passive"))
      (node (ref "R40") (pin "1") (pinfunction "1_1") (pintype "passive"))
      (node (ref "U12") (pin "7") (pinfunction "SET_7") (pintype "passive"))
    )
    (net (code "165") (name "Net-(U14-OD)") (class "Default")
      (node (ref "R44") (pin "1") (pinfunction "1_1") (pintype "passive"))
      (node (ref "U14") (pin "9") (pinfunction "OD_9") (pintype "passive"))
    )
    (net (code "166") (name "Net-(U14-SET)") (class "Default")
      (node (ref "K4") (pin "3") (pinfunction "3_3") (pintype "passive"))
      (node (ref "R45") (pin "1") (pinfunction "1_1") (pintype "passive"))
      (node (ref "U14") (pin "7") (pinfunction "SET_7") (pintype "passive"))
    )
    (net (code "167") (name "Net-(U15-OD)") (class "Default")
      (node (ref "R49") (pin "1") (pinfunction "1_1") (pintype "passive"))
      (node (ref "U15") (pin "9") (pinfunction "OD_9") (pintype "passive"))
    )
    (net (code "168") (name "Net-(U15-SET)") (class "Default")
      (node (ref "K5") (pin "3") (pinfunction "3_3") (pintype "passive"))
      (node (ref "R50") (pin "1") (pinfunction "1_1") (pintype "passive"))
      (node (ref "U15") (pin "7") (pinfunction "SET_7") (pintype "passive"))
    )
    (net (code "169") (name "Net-(U16-7C)") (class "Default")
      (node (ref "K1") (pin "1") (pinfunction "1_1") (pintype "passive"))
      (node (ref "U16") (pin "10") (pinfunction "7C_10") (pintype "passive"))
    )
    (net (code "170") (name "unconnected-(M1-GPIO0-Pad11)") (class "Default")
      (node (ref "M1") (pin "11") (pinfunction "GPIO0_11") (pintype "passive+no_connect"))
    )
    (net (code "171") (name "unconnected-(M1-GPIO1-Pad10)") (class "Default")
      (node (ref "M1") (pin "10") (pinfunction "GPIO1_10") (pintype "passive+no_connect"))
    )
    (net (code "172") (name "unconnected-(M1-GPIO2-Pad4)") (class "Default")
      (node (ref "M1") (pin "4") (pinfunction "GPIO2_4") (pintype "passive+no_connect"))
    )
    (net (code "173") (name "unconnected-(M1-GPIO3-Pad3)") (class "Default")
      (node (ref "M1") (pin "3") (pinfunction "GPIO3_3") (pintype "passive+no_connect"))
    )
    (net (code "174") (name "unconnected-(P9-ID-Pad4)") (class "Default")
      (node (ref "P9") (pin "4") (pinfunction "ID_4") (pintype "passive"))
    )
    (net (code "175") (name "unconnected-(U1-CF-Pad6)") (class "Default")
      (node (ref "U1") (pin "6") (pinfunction "CF_6") (pintype "passive+no_connect"))
    )
    (net (code "176") (name "unconnected-(U1-SEL-Pad8)") (class "Default")
      (node (ref "U1") (pin "8") (pinfunction "SEL_8") (pintype "passive+no_connect"))
    )
    (net (code "177") (name "unconnected-(U1-V2P-Pad4)") (class "Default")
      (node (ref "U1") (pin "4") (pinfunction "V2P_4") (pintype "passive+no_connect"))
    )
    (net (code "178") (name "unconnected-(U2-NC-Pad6)") (class "Default")
      (node (ref "U2") (pin "6") (pinfunction "NC_6") (pintype "passive+no_connect"))
    )
    (net (code "179") (name "unconnected-(U7-1B-Pad1)") (class "Default")
      (node (ref "U7") (pin "1") (pinfunction "1B_1") (pintype "passive"))
    )
    (net (code "180") (name "unconnected-(U7-1C-Pad16)") (class "Default")
      (node (ref "U7") (pin "16") (pinfunction "1C_16") (pintype "passive"))
    )
    (net (code "181") (name "unconnected-(U7-2B-Pad2)") (class "Default")
      (node (ref "U7") (pin "2") (pinfunction "2B_2") (pintype "passive"))
    )
    (net (code "182") (name "unconnected-(U7-2C-Pad15)") (class "Default")
      (node (ref "U7") (pin "15") (pinfunction "2C_15") (pintype "passive"))
    )
    (net (code "183") (name "unconnected-(U7-3B-Pad3)") (class "Default")
      (node (ref "U7") (pin "3") (pinfunction "3B_3") (pintype "passive"))
    )
    (net (code "184") (name "unconnected-(U7-3C-Pad14)") (class "Default")
      (node (ref "U7") (pin "14") (pinfunction "3C_14") (pintype "passive"))
    )
    (net (code "185") (name "unconnected-(U8-PA9{slash}USART1_TX{slash}TIM1_CH2{slash}I2C3_SMBA{slash}DCMI_D0{slash}EVENTOUT{slash}OTG_FS_VBUS-Pad68)") (class "Default")
      (node (ref "U8") (pin "68") (pinfunction "PA9/USART1_TX/TIM1_CH2/I2C3_SMBA/DCMI_D0/EVENTOUT/OTG_FS_VBUS_68") (pintype "bidirectional"))
    )
    (net (code "186") (name "unconnected-(U8-PB1{slash}TIM3_CH4{slash}TIM8_CH3N{slash}OTG_HS_ULPI_D2{slash}ETH_MII_RXD3{slash}OTG_HS_INTN{slash}TIM1_CH3N{slash}EVENTOUT{slash}ADC12_IN9-Pad36)") (class "Default")
      (node (ref "U8") (pin "36") (pinfunction "PB1/TIM3_CH4/TIM8_CH3N/OTG_HS_ULPI_D2/ETH_MII_RXD3/OTG_HS_INTN/TIM1_CH3N/EVENTOUT/ADC12_IN9_36") (pintype "bidirectional"))
    )
    (net (code "187") (name "unconnected-(U8-PB7{slash}I2C1_SDA{slash}FSMC_NL{slash}DCMI_VSYNC{slash}USART1_RX{slash}TIM4_CH2{slash}EVENTOUT-Pad93)") (class "Default")
      (node (ref "U8") (pin "93") (pinfunction "PB7/I2C1_SDA/FSMC_NL/DCMI_VSYNC/USART1_RX/TIM4_CH2/EVENTOUT_93") (pintype "bidirectional"))
    )
    (net (code "188") (name "unconnected-(U8-PB8{slash}TIM4_CH3{slash}SDIO_D4{slash}TIM10_CH1{slash}DCMI_D6{slash}ETH_MII_TXD3{slash}I2C1_SCL{slash}CAN1_RX{slash}EVENTOUT-Pad95)") (class "Default")
      (node (ref "U8") (pin "95") (pinfunction "PB8/TIM4_CH3/SDIO_D4/TIM10_CH1/DCMI_D6/ETH_MII_TXD3/I2C1_SCL/CAN1_RX/EVENTOUT_95") (pintype "bidirectional"))
    )
    (net (code "189") (name "unconnected-(U8-PC3{slash}SPI2_MOSI{slash}I2S2_SD{slash}OTG_HS_ULPI_NXT{slash}ETH_MII_TX_CLK{slash}EVENTOUT{slash}ADC123_IN13-Pad18)") (class "Default")
      (node (ref "U8") (pin "18") (pinfunction "PC3/SPI2_MOSI/I2S2_SD/OTG_HS_ULPI_NXT/ETH_MII_TX_CLK/EVENTOUT/ADC123_IN13_18") (pintype "bidirectional"))
    )
    (net (code "190") (name "unconnected-(U8-PD12{slash}FSMC_ALE{slash}FSMC_A17{slash}TIM4_CH1{slash}USART3_RTS{slash}EVENTOUT-Pad59)") (class "Default")
      (node (ref "U8") (pin "59") (pinfunction "PD12/FSMC_ALE/FSMC_A17/TIM4_CH1/USART3_RTS/EVENTOUT_59") (pintype "bidirectional"))
    )
    (net (code "191") (name "unconnected-(U8-PD13{slash}FSMC_A18{slash}TIM4_CH2{slash}EVENTOUT-Pad60)") (class "Default")
      (node (ref "U8") (pin "60") (pinfunction "PD13/FSMC_A18/TIM4_CH2/EVENTOUT_60") (pintype "bidirectional"))
    )
    (net (code "192") (name "unconnected-(U10-REGF-Pad5)") (class "Default")
      (node (ref "U10") (pin "5") (pinfunction "REGF_5") (pintype "passive+no_connect"))
    )
    (net (code "193") (name "unconnected-(U10-REGS-Pad4)") (class "Default")
      (node (ref "U10") (pin "4") (pinfunction "REGS_4") (pintype "passive+no_connect"))
    )
    (net (code "194") (name "unconnected-(U10-~{EF}-Pad8)") (class "Default")
      (node (ref "U10") (pin "8") (pinfunction "~{EF}_8") (pintype "passive+no_connect"))
    )
    (net (code "195") (name "unconnected-(U12-REGF-Pad5)") (class "Default")
      (node (ref "U12") (pin "5") (pinfunction "REGF_5") (pintype "passive+no_connect"))
    )
    (net (code "196") (name "unconnected-(U12-REGS-Pad4)") (class "Default")
      (node (ref "U12") (pin "4") (pinfunction "REGS_4") (pintype "passive+no_connect"))
    )
    (net (code "197") (name "unconnected-(U12-~{EF}-Pad8)") (class "Default")
      (node (ref "U12") (pin "8") (pinfunction "~{EF}_8") (pintype "passive+no_connect"))
    )
    (net (code "198") (name "unconnected-(U14-REGF-Pad5)") (class "Default")
      (node (ref "U14") (pin "5") (pinfunction "REGF_5") (pintype "passive+no_connect"))
    )
    (net (code "199") (name "unconnected-(U14-REGS-Pad4)") (class "Default")
      (node (ref "U14") (pin "4") (pinfunction "REGS_4") (pintype "passive+no_connect"))
    )
    (net (code "200") (name "unconnected-(U14-~{EF}-Pad8)") (class "Default")
      (node (ref "U14") (pin "8") (pinfunction "~{EF}_8") (pintype "passive+no_connect"))
    )
    (net (code "201") (name "unconnected-(U15-REGF-Pad5)") (class "Default")
      (node (ref "U15") (pin "5") (pinfunction "REGF_5") (pintype "passive+no_connect"))
    )
    (net (code "202") (name "unconnected-(U15-REGS-Pad4)") (class "Default")
      (node (ref "U15") (pin "4") (pinfunction "REGS_4") (pintype "passive+no_connect"))
    )
    (net (code "203") (name "unconnected-(U15-~{EF}-Pad8)") (class "Default")
      (node (ref "U15") (pin "8") (pinfunction "~{EF}_8") (pintype "passive+no_connect"))
    )
    (net (code "204") (name "unconnected-(U16-4B-Pad4)") (class "Default")
      (node (ref "U16") (pin "4") (pinfunction "4B_4") (pintype "passive"))
    )
    (net (code "205") (name "unconnected-(U16-4C-Pad13)") (class "Default")
      (node (ref "U16") (pin "13") (pinfunction "4C_13") (pintype "passive"))
    )
  )
)
